# USB_SATA.net
KiCad netlist of a schematic drawn in Altium Designer
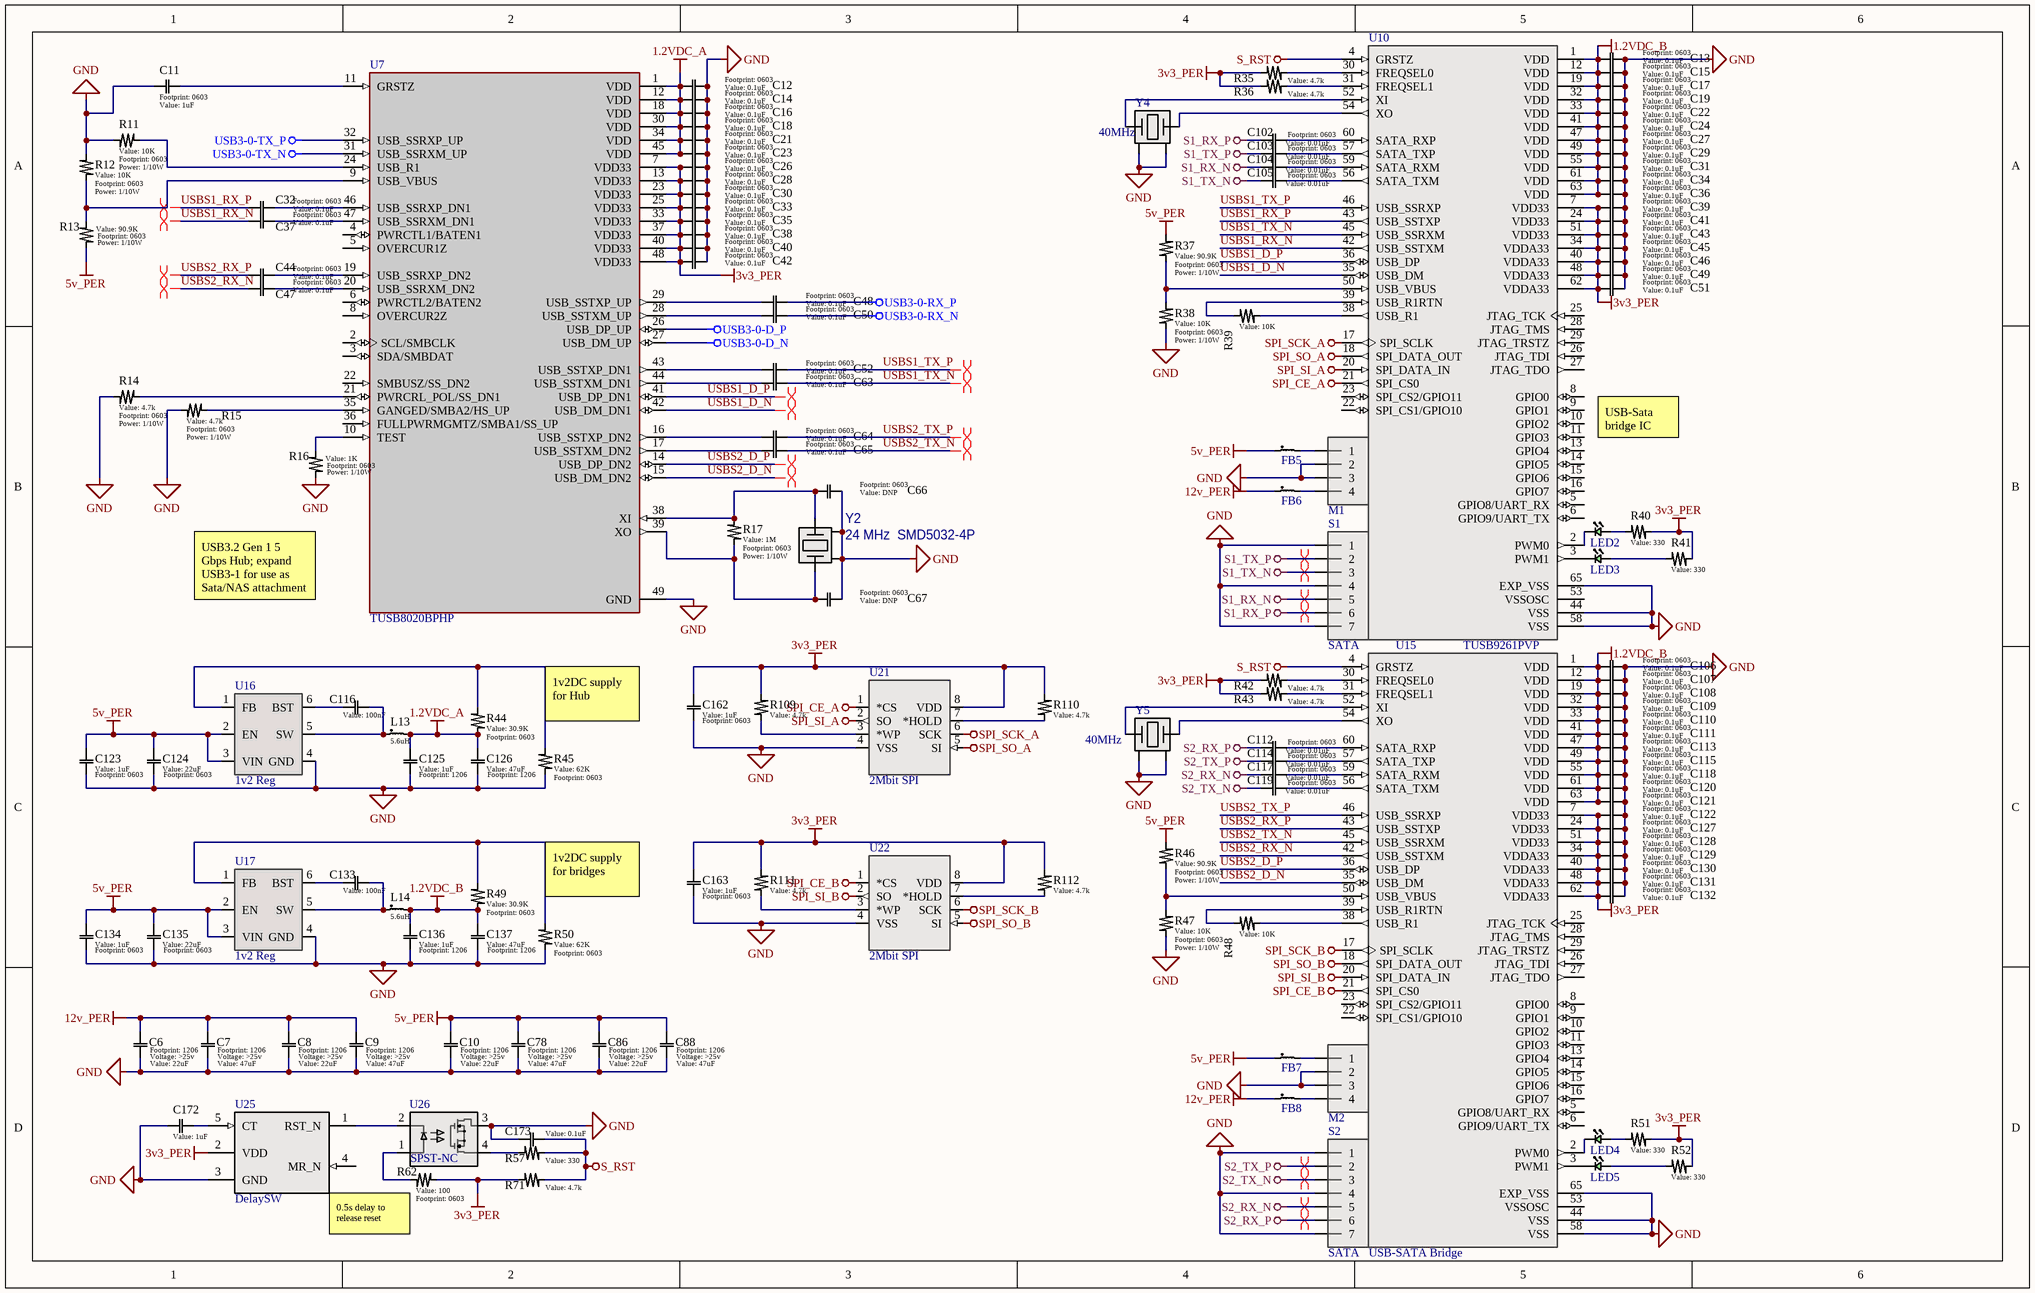
[diagram p0: USB_SATA.SchDoc]

(export (version "E")
  (design (tool "Eeschema 10.0.6"))
  (components
    (comp (ref "C6")
      (value "22uF")
      (footprint "1206")
      (fields
        (field (name "VOLTAGE") ">25v")
        (field (name "TOLERANCE") "20%")
        (field (name "Comment") "Generic Capacitor")
      )
      (libsource (lib "Capacitors") (part "Generic Capacitor"))
    )
    (comp (ref "C7")
      (value "47uF")
      (footprint "1206")
      (fields
        (field (name "VOLTAGE") ">25v")
        (field (name "TOLERANCE") "20%")
        (field (name "Comment") "Generic Capacitor")
      )
      (libsource (lib "Capacitors") (part "Generic Capacitor"))
    )
    (comp (ref "C8")
      (value "22uF")
      (footprint "1206")
      (fields
        (field (name "VOLTAGE") ">25v")
        (field (name "TOLERANCE") "20%")
        (field (name "Comment") "Generic Capacitor")
      )
      (libsource (lib "Capacitors") (part "Generic Capacitor"))
    )
    (comp (ref "C9")
      (value "47uF")
      (footprint "1206")
      (fields
        (field (name "VOLTAGE") ">25v")
        (field (name "TOLERANCE") "20%")
        (field (name "Comment") "Generic Capacitor")
      )
      (libsource (lib "Capacitors") (part "Generic Capacitor"))
    )
    (comp (ref "C10")
      (value "22uF")
      (footprint "1206")
      (fields
        (field (name "VOLTAGE") ">25v")
        (field (name "TOLERANCE") "20%")
        (field (name "Comment") "Generic Capacitor")
      )
      (libsource (lib "Capacitors") (part "Generic Capacitor"))
    )
    (comp (ref "C11")
      (value "1uF")
      (footprint "0603")
      (fields
        (field (name "VOLTAGE") ">10V")
        (field (name "TOLERANCE") "10%")
        (field (name "Comment") "Generic Capacitor")
      )
      (libsource (lib "Capacitors") (part "Generic Capacitor"))
    )
    (comp (ref "C12")
      (value "0.1uF")
      (footprint "0603")
      (fields
        (field (name "VOLTAGE") "10V")
        (field (name "TOLERANCE") "10%")
        (field (name "Comment") "Generic Capacitor")
      )
      (libsource (lib "Capacitors") (part "Generic Capacitor"))
    )
    (comp (ref "C13")
      (value "0.1uF")
      (footprint "0603")
      (fields
        (field (name "VOLTAGE") "10V")
        (field (name "TOLERANCE") "10%")
        (field (name "Comment") "Generic Capacitor")
      )
      (libsource (lib "Capacitors") (part "Generic Capacitor"))
    )
    (comp (ref "C14")
      (value "0.1uF")
      (footprint "0603")
      (fields
        (field (name "VOLTAGE") "10V")
        (field (name "TOLERANCE") "10%")
        (field (name "Comment") "Generic Capacitor")
      )
      (libsource (lib "Capacitors") (part "Generic Capacitor"))
    )
    (comp (ref "C15")
      (value "0.1uF")
      (footprint "0603")
      (fields
        (field (name "VOLTAGE") "10V")
        (field (name "TOLERANCE") "10%")
        (field (name "Comment") "Generic Capacitor")
      )
      (libsource (lib "Capacitors") (part "Generic Capacitor"))
    )
    (comp (ref "C16")
      (value "0.1uF")
      (footprint "0603")
      (fields
        (field (name "VOLTAGE") "10V")
        (field (name "TOLERANCE") "10%")
        (field (name "Comment") "Generic Capacitor")
      )
      (libsource (lib "Capacitors") (part "Generic Capacitor"))
    )
    (comp (ref "C17")
      (value "0.1uF")
      (footprint "0603")
      (fields
        (field (name "VOLTAGE") "10V")
        (field (name "TOLERANCE") "10%")
        (field (name "Comment") "Generic Capacitor")
      )
      (libsource (lib "Capacitors") (part "Generic Capacitor"))
    )
    (comp (ref "C18")
      (value "0.1uF")
      (footprint "0603")
      (fields
        (field (name "VOLTAGE") "10V")
        (field (name "TOLERANCE") "10%")
        (field (name "Comment") "Generic Capacitor")
      )
      (libsource (lib "Capacitors") (part "Generic Capacitor"))
    )
    (comp (ref "C19")
      (value "0.1uF")
      (footprint "0603")
      (fields
        (field (name "VOLTAGE") "10V")
        (field (name "TOLERANCE") "10%")
        (field (name "Comment") "Generic Capacitor")
      )
      (libsource (lib "Capacitors") (part "Generic Capacitor"))
    )
    (comp (ref "C21")
      (value "0.1uF")
      (footprint "0603")
      (fields
        (field (name "VOLTAGE") "10V")
        (field (name "TOLERANCE") "10%")
        (field (name "Comment") "Generic Capacitor")
      )
      (libsource (lib "Capacitors") (part "Generic Capacitor"))
    )
    (comp (ref "C22")
      (value "0.1uF")
      (footprint "0603")
      (fields
        (field (name "VOLTAGE") "10V")
        (field (name "TOLERANCE") "10%")
        (field (name "Comment") "Generic Capacitor")
      )
      (libsource (lib "Capacitors") (part "Generic Capacitor"))
    )
    (comp (ref "C23")
      (value "0.1uF")
      (footprint "0603")
      (fields
        (field (name "VOLTAGE") "10V")
        (field (name "TOLERANCE") "10%")
        (field (name "Comment") "Generic Capacitor")
      )
      (libsource (lib "Capacitors") (part "Generic Capacitor"))
    )
    (comp (ref "C24")
      (value "0.1uF")
      (footprint "0603")
      (fields
        (field (name "VOLTAGE") "10V")
        (field (name "TOLERANCE") "10%")
        (field (name "Comment") "Generic Capacitor")
      )
      (libsource (lib "Capacitors") (part "Generic Capacitor"))
    )
    (comp (ref "C26")
      (value "0.1uF")
      (footprint "0603")
      (fields
        (field (name "VOLTAGE") "10V")
        (field (name "TOLERANCE") "10%")
        (field (name "Comment") "Generic Capacitor")
      )
      (libsource (lib "Capacitors") (part "Generic Capacitor"))
    )
    (comp (ref "C27")
      (value "0.1uF")
      (footprint "0603")
      (fields
        (field (name "VOLTAGE") "10V")
        (field (name "TOLERANCE") "10%")
        (field (name "Comment") "Generic Capacitor")
      )
      (libsource (lib "Capacitors") (part "Generic Capacitor"))
    )
    (comp (ref "C28")
      (value "0.1uF")
      (footprint "0603")
      (fields
        (field (name "VOLTAGE") "10V")
        (field (name "TOLERANCE") "10%")
        (field (name "Comment") "Generic Capacitor")
      )
      (libsource (lib "Capacitors") (part "Generic Capacitor"))
    )
    (comp (ref "C29")
      (value "0.1uF")
      (footprint "0603")
      (fields
        (field (name "VOLTAGE") "10V")
        (field (name "TOLERANCE") "10%")
        (field (name "Comment") "Generic Capacitor")
      )
      (libsource (lib "Capacitors") (part "Generic Capacitor"))
    )
    (comp (ref "C30")
      (value "0.1uF")
      (footprint "0603")
      (fields
        (field (name "VOLTAGE") "10V")
        (field (name "TOLERANCE") "10%")
        (field (name "Comment") "Generic Capacitor")
      )
      (libsource (lib "Capacitors") (part "Generic Capacitor"))
    )
    (comp (ref "C31")
      (value "0.1uF")
      (footprint "0603")
      (fields
        (field (name "VOLTAGE") "10V")
        (field (name "TOLERANCE") "10%")
        (field (name "Comment") "Generic Capacitor")
      )
      (libsource (lib "Capacitors") (part "Generic Capacitor"))
    )
    (comp (ref "C32")
      (value "0.1uF")
      (footprint "0603")
      (fields
        (field (name "VOLTAGE") "10V")
        (field (name "TOLERANCE") "10%")
        (field (name "Comment") "Generic Capacitor")
      )
      (libsource (lib "Capacitors") (part "Generic Capacitor"))
    )
    (comp (ref "C33")
      (value "0.1uF")
      (footprint "0603")
      (fields
        (field (name "VOLTAGE") "10V")
        (field (name "TOLERANCE") "10%")
        (field (name "Comment") "Generic Capacitor")
      )
      (libsource (lib "Capacitors") (part "Generic Capacitor"))
    )
    (comp (ref "C34")
      (value "0.1uF")
      (footprint "0603")
      (fields
        (field (name "VOLTAGE") "10V")
        (field (name "TOLERANCE") "10%")
        (field (name "Comment") "Generic Capacitor")
      )
      (libsource (lib "Capacitors") (part "Generic Capacitor"))
    )
    (comp (ref "C35")
      (value "0.1uF")
      (footprint "0603")
      (fields
        (field (name "VOLTAGE") "10V")
        (field (name "TOLERANCE") "10%")
        (field (name "Comment") "Generic Capacitor")
      )
      (libsource (lib "Capacitors") (part "Generic Capacitor"))
    )
    (comp (ref "C36")
      (value "0.1uF")
      (footprint "0603")
      (fields
        (field (name "VOLTAGE") "10V")
        (field (name "TOLERANCE") "10%")
        (field (name "Comment") "Generic Capacitor")
      )
      (libsource (lib "Capacitors") (part "Generic Capacitor"))
    )
    (comp (ref "C37")
      (value "0.1uF")
      (footprint "0603")
      (fields
        (field (name "VOLTAGE") "10V")
        (field (name "TOLERANCE") "10%")
        (field (name "Comment") "Generic Capacitor")
      )
      (libsource (lib "Capacitors") (part "Generic Capacitor"))
    )
    (comp (ref "C38")
      (value "0.1uF")
      (footprint "0603")
      (fields
        (field (name "VOLTAGE") "10V")
        (field (name "TOLERANCE") "10%")
        (field (name "Comment") "Generic Capacitor")
      )
      (libsource (lib "Capacitors") (part "Generic Capacitor"))
    )
    (comp (ref "C39")
      (value "0.1uF")
      (footprint "0603")
      (fields
        (field (name "VOLTAGE") "10V")
        (field (name "TOLERANCE") "10%")
        (field (name "Comment") "Generic Capacitor")
      )
      (libsource (lib "Capacitors") (part "Generic Capacitor"))
    )
    (comp (ref "C40")
      (value "0.1uF")
      (footprint "0603")
      (fields
        (field (name "VOLTAGE") "10V")
        (field (name "TOLERANCE") "10%")
        (field (name "Comment") "Generic Capacitor")
      )
      (libsource (lib "Capacitors") (part "Generic Capacitor"))
    )
    (comp (ref "C41")
      (value "0.1uF")
      (footprint "0603")
      (fields
        (field (name "VOLTAGE") "10V")
        (field (name "TOLERANCE") "10%")
        (field (name "Comment") "Generic Capacitor")
      )
      (libsource (lib "Capacitors") (part "Generic Capacitor"))
    )
    (comp (ref "C42")
      (value "0.1uF")
      (footprint "0603")
      (fields
        (field (name "VOLTAGE") "10V")
        (field (name "TOLERANCE") "10%")
        (field (name "Comment") "Generic Capacitor")
      )
      (libsource (lib "Capacitors") (part "Generic Capacitor"))
    )
    (comp (ref "C43")
      (value "0.1uF")
      (footprint "0603")
      (fields
        (field (name "VOLTAGE") "10V")
        (field (name "TOLERANCE") "10%")
        (field (name "Comment") "Generic Capacitor")
      )
      (libsource (lib "Capacitors") (part "Generic Capacitor"))
    )
    (comp (ref "C44")
      (value "0.1uF")
      (footprint "0603")
      (fields
        (field (name "VOLTAGE") "10V")
        (field (name "TOLERANCE") "10%")
        (field (name "Comment") "Generic Capacitor")
      )
      (libsource (lib "Capacitors") (part "Generic Capacitor"))
    )
    (comp (ref "C45")
      (value "0.1uF")
      (footprint "0603")
      (fields
        (field (name "VOLTAGE") "10V")
        (field (name "TOLERANCE") "10%")
        (field (name "Comment") "Generic Capacitor")
      )
      (libsource (lib "Capacitors") (part "Generic Capacitor"))
    )
    (comp (ref "C46")
      (value "0.1uF")
      (footprint "0603")
      (fields
        (field (name "VOLTAGE") "10V")
        (field (name "TOLERANCE") "10%")
        (field (name "Comment") "Generic Capacitor")
      )
      (libsource (lib "Capacitors") (part "Generic Capacitor"))
    )
    (comp (ref "C47")
      (value "0.1uF")
      (footprint "0603")
      (fields
        (field (name "VOLTAGE") "10V")
        (field (name "TOLERANCE") "10%")
        (field (name "Comment") "Generic Capacitor")
      )
      (libsource (lib "Capacitors") (part "Generic Capacitor"))
    )
    (comp (ref "C48")
      (value "0.1uF")
      (footprint "0603")
      (fields
        (field (name "VOLTAGE") "10V")
        (field (name "TOLERANCE") "10%")
        (field (name "Comment") "Generic Capacitor")
      )
      (libsource (lib "Capacitors") (part "Generic Capacitor"))
    )
    (comp (ref "C49")
      (value "0.1uF")
      (footprint "0603")
      (fields
        (field (name "VOLTAGE") "10V")
        (field (name "TOLERANCE") "10%")
        (field (name "Comment") "Generic Capacitor")
      )
      (libsource (lib "Capacitors") (part "Generic Capacitor"))
    )
    (comp (ref "C50")
      (value "0.1uF")
      (footprint "0603")
      (fields
        (field (name "VOLTAGE") "10V")
        (field (name "TOLERANCE") "10%")
        (field (name "Comment") "Generic Capacitor")
      )
      (libsource (lib "Capacitors") (part "Generic Capacitor"))
    )
    (comp (ref "C51")
      (value "0.1uF")
      (footprint "0603")
      (fields
        (field (name "VOLTAGE") "10V")
        (field (name "TOLERANCE") "10%")
        (field (name "Comment") "Generic Capacitor")
      )
      (libsource (lib "Capacitors") (part "Generic Capacitor"))
    )
    (comp (ref "C52")
      (value "0.1uF")
      (footprint "0603")
      (fields
        (field (name "VOLTAGE") "10V")
        (field (name "TOLERANCE") "10%")
        (field (name "Comment") "Generic Capacitor")
      )
      (libsource (lib "Capacitors") (part "Generic Capacitor"))
    )
    (comp (ref "C63")
      (value "0.1uF")
      (footprint "0603")
      (fields
        (field (name "VOLTAGE") "10V")
        (field (name "TOLERANCE") "10%")
        (field (name "Comment") "Generic Capacitor")
      )
      (libsource (lib "Capacitors") (part "Generic Capacitor"))
    )
    (comp (ref "C64")
      (value "0.1uF")
      (footprint "0603")
      (fields
        (field (name "VOLTAGE") "10V")
        (field (name "TOLERANCE") "10%")
        (field (name "Comment") "Generic Capacitor")
      )
      (libsource (lib "Capacitors") (part "Generic Capacitor"))
    )
    (comp (ref "C65")
      (value "0.1uF")
      (footprint "0603")
      (fields
        (field (name "VOLTAGE") "10V")
        (field (name "TOLERANCE") "10%")
        (field (name "Comment") "Generic Capacitor")
      )
      (libsource (lib "Capacitors") (part "Generic Capacitor"))
    )
    (comp (ref "C66")
      (value "DNP")
      (footprint "0603")
      (fields
        (field (name "VOLTAGE") ">10V")
        (field (name "TOLERANCE") "10%")
        (field (name "Comment") "Generic Capacitor")
      )
      (libsource (lib "Capacitors") (part "Generic Capacitor"))
    )
    (comp (ref "C67")
      (value "DNP")
      (footprint "0603")
      (fields
        (field (name "VOLTAGE") ">10V")
        (field (name "TOLERANCE") "10%")
        (field (name "Comment") "Generic Capacitor")
      )
      (libsource (lib "Capacitors") (part "Generic Capacitor"))
    )
    (comp (ref "C78")
      (value "47uF")
      (footprint "1206")
      (fields
        (field (name "VOLTAGE") ">25v")
        (field (name "TOLERANCE") "20%")
        (field (name "Comment") "Generic Capacitor")
      )
      (libsource (lib "Capacitors") (part "Generic Capacitor"))
    )
    (comp (ref "C86")
      (value "22uF")
      (footprint "1206")
      (fields
        (field (name "VOLTAGE") ">25v")
        (field (name "TOLERANCE") "20%")
        (field (name "Comment") "Generic Capacitor")
      )
      (libsource (lib "Capacitors") (part "Generic Capacitor"))
    )
    (comp (ref "C88")
      (value "47uF")
      (footprint "1206")
      (fields
        (field (name "VOLTAGE") ">25v")
        (field (name "TOLERANCE") "20%")
        (field (name "Comment") "Generic Capacitor")
      )
      (libsource (lib "Capacitors") (part "Generic Capacitor"))
    )
    (comp (ref "C102")
      (value "0.01uF")
      (footprint "0603")
      (fields
        (field (name "VOLTAGE") "10V")
        (field (name "TOLERANCE") "10%")
        (field (name "Comment") "Generic Capacitor")
      )
      (libsource (lib "Capacitors") (part "Generic Capacitor"))
    )
    (comp (ref "C103")
      (value "0.01uF")
      (footprint "0603")
      (fields
        (field (name "VOLTAGE") "10V")
        (field (name "TOLERANCE") "10%")
        (field (name "Comment") "Generic Capacitor")
      )
      (libsource (lib "Capacitors") (part "Generic Capacitor"))
    )
    (comp (ref "C104")
      (value "0.01uF")
      (footprint "0603")
      (fields
        (field (name "VOLTAGE") "10V")
        (field (name "TOLERANCE") "10%")
        (field (name "Comment") "Generic Capacitor")
      )
      (libsource (lib "Capacitors") (part "Generic Capacitor"))
    )
    (comp (ref "C105")
      (value "0.01uF")
      (footprint "0603")
      (fields
        (field (name "VOLTAGE") "10V")
        (field (name "TOLERANCE") "10%")
        (field (name "Comment") "Generic Capacitor")
      )
      (libsource (lib "Capacitors") (part "Generic Capacitor"))
    )
    (comp (ref "C106")
      (value "0.1uF")
      (footprint "0603")
      (fields
        (field (name "VOLTAGE") "10V")
        (field (name "TOLERANCE") "10%")
        (field (name "Comment") "Generic Capacitor")
      )
      (libsource (lib "Capacitors") (part "Generic Capacitor"))
    )
    (comp (ref "C107")
      (value "0.1uF")
      (footprint "0603")
      (fields
        (field (name "VOLTAGE") "10V")
        (field (name "TOLERANCE") "10%")
        (field (name "Comment") "Generic Capacitor")
      )
      (libsource (lib "Capacitors") (part "Generic Capacitor"))
    )
    (comp (ref "C108")
      (value "0.1uF")
      (footprint "0603")
      (fields
        (field (name "VOLTAGE") "10V")
        (field (name "TOLERANCE") "10%")
        (field (name "Comment") "Generic Capacitor")
      )
      (libsource (lib "Capacitors") (part "Generic Capacitor"))
    )
    (comp (ref "C109")
      (value "0.1uF")
      (footprint "0603")
      (fields
        (field (name "VOLTAGE") "10V")
        (field (name "TOLERANCE") "10%")
        (field (name "Comment") "Generic Capacitor")
      )
      (libsource (lib "Capacitors") (part "Generic Capacitor"))
    )
    (comp (ref "C110")
      (value "0.1uF")
      (footprint "0603")
      (fields
        (field (name "VOLTAGE") "10V")
        (field (name "TOLERANCE") "10%")
        (field (name "Comment") "Generic Capacitor")
      )
      (libsource (lib "Capacitors") (part "Generic Capacitor"))
    )
    (comp (ref "C111")
      (value "0.1uF")
      (footprint "0603")
      (fields
        (field (name "VOLTAGE") "10V")
        (field (name "TOLERANCE") "10%")
        (field (name "Comment") "Generic Capacitor")
      )
      (libsource (lib "Capacitors") (part "Generic Capacitor"))
    )
    (comp (ref "C112")
      (value "0.01uF")
      (footprint "0603")
      (fields
        (field (name "VOLTAGE") "10V")
        (field (name "TOLERANCE") "10%")
        (field (name "Comment") "Generic Capacitor")
      )
      (libsource (lib "Capacitors") (part "Generic Capacitor"))
    )
    (comp (ref "C113")
      (value "0.1uF")
      (footprint "0603")
      (fields
        (field (name "VOLTAGE") "10V")
        (field (name "TOLERANCE") "10%")
        (field (name "Comment") "Generic Capacitor")
      )
      (libsource (lib "Capacitors") (part "Generic Capacitor"))
    )
    (comp (ref "C114")
      (value "0.01uF")
      (footprint "0603")
      (fields
        (field (name "VOLTAGE") "10V")
        (field (name "TOLERANCE") "10%")
        (field (name "Comment") "Generic Capacitor")
      )
      (libsource (lib "Capacitors") (part "Generic Capacitor"))
    )
    (comp (ref "C115")
      (value "0.1uF")
      (footprint "0603")
      (fields
        (field (name "VOLTAGE") "10V")
        (field (name "TOLERANCE") "10%")
        (field (name "Comment") "Generic Capacitor")
      )
      (libsource (lib "Capacitors") (part "Generic Capacitor"))
    )
    (comp (ref "C116")
      (value "100nF")
      (footprint "0603")
      (fields
        (field (name "VOLTAGE") ">10V")
        (field (name "TOLERANCE") "10%")
        (field (name "Comment") "Generic Capacitor")
      )
      (libsource (lib "Capacitors") (part "Generic Capacitor"))
    )
    (comp (ref "C117")
      (value "0.01uF")
      (footprint "0603")
      (fields
        (field (name "VOLTAGE") "10V")
        (field (name "TOLERANCE") "10%")
        (field (name "Comment") "Generic Capacitor")
      )
      (libsource (lib "Capacitors") (part "Generic Capacitor"))
    )
    (comp (ref "C118")
      (value "0.1uF")
      (footprint "0603")
      (fields
        (field (name "VOLTAGE") "10V")
        (field (name "TOLERANCE") "10%")
        (field (name "Comment") "Generic Capacitor")
      )
      (libsource (lib "Capacitors") (part "Generic Capacitor"))
    )
    (comp (ref "C119")
      (value "0.01uF")
      (footprint "0603")
      (fields
        (field (name "VOLTAGE") "10V")
        (field (name "TOLERANCE") "10%")
        (field (name "Comment") "Generic Capacitor")
      )
      (libsource (lib "Capacitors") (part "Generic Capacitor"))
    )
    (comp (ref "C120")
      (value "0.1uF")
      (footprint "0603")
      (fields
        (field (name "VOLTAGE") "10V")
        (field (name "TOLERANCE") "10%")
        (field (name "Comment") "Generic Capacitor")
      )
      (libsource (lib "Capacitors") (part "Generic Capacitor"))
    )
    (comp (ref "C121")
      (value "0.1uF")
      (footprint "0603")
      (fields
        (field (name "VOLTAGE") "10V")
        (field (name "TOLERANCE") "10%")
        (field (name "Comment") "Generic Capacitor")
      )
      (libsource (lib "Capacitors") (part "Generic Capacitor"))
    )
    (comp (ref "C122")
      (value "0.1uF")
      (footprint "0603")
      (fields
        (field (name "VOLTAGE") "10V")
        (field (name "TOLERANCE") "10%")
        (field (name "Comment") "Generic Capacitor")
      )
      (libsource (lib "Capacitors") (part "Generic Capacitor"))
    )
    (comp (ref "C123")
      (value "1uF")
      (footprint "0603")
      (fields
        (field (name "VOLTAGE") ">10V")
        (field (name "TOLERANCE") "10%")
        (field (name "Comment") "Generic Capacitor")
      )
      (libsource (lib "Capacitors") (part "Generic Capacitor"))
    )
    (comp (ref "C124")
      (value "22uF")
      (footprint "0603")
      (fields
        (field (name "VOLTAGE") ">10V")
        (field (name "TOLERANCE") "10%")
        (field (name "Comment") "Generic Capacitor")
      )
      (libsource (lib "Capacitors") (part "Generic Capacitor"))
    )
    (comp (ref "C125")
      (value "1uF")
      (footprint "1206")
      (fields
        (field (name "VOLTAGE") ">10V")
        (field (name "TOLERANCE") "10%")
        (field (name "Comment") "Generic Capacitor")
      )
      (libsource (lib "Capacitors") (part "Generic Capacitor"))
    )
    (comp (ref "C126")
      (value "47uF")
      (footprint "1206")
      (fields
        (field (name "VOLTAGE") ">10V")
        (field (name "TOLERANCE") "10%")
        (field (name "Comment") "Generic Capacitor")
      )
      (libsource (lib "Capacitors") (part "Generic Capacitor"))
    )
    (comp (ref "C127")
      (value "0.1uF")
      (footprint "0603")
      (fields
        (field (name "VOLTAGE") "10V")
        (field (name "TOLERANCE") "10%")
        (field (name "Comment") "Generic Capacitor")
      )
      (libsource (lib "Capacitors") (part "Generic Capacitor"))
    )
    (comp (ref "C128")
      (value "0.1uF")
      (footprint "0603")
      (fields
        (field (name "VOLTAGE") "10V")
        (field (name "TOLERANCE") "10%")
        (field (name "Comment") "Generic Capacitor")
      )
      (libsource (lib "Capacitors") (part "Generic Capacitor"))
    )
    (comp (ref "C129")
      (value "0.1uF")
      (footprint "0603")
      (fields
        (field (name "VOLTAGE") "10V")
        (field (name "TOLERANCE") "10%")
        (field (name "Comment") "Generic Capacitor")
      )
      (libsource (lib "Capacitors") (part "Generic Capacitor"))
    )
    (comp (ref "C130")
      (value "0.1uF")
      (footprint "0603")
      (fields
        (field (name "VOLTAGE") "10V")
        (field (name "TOLERANCE") "10%")
        (field (name "Comment") "Generic Capacitor")
      )
      (libsource (lib "Capacitors") (part "Generic Capacitor"))
    )
    (comp (ref "C131")
      (value "0.1uF")
      (footprint "0603")
      (fields
        (field (name "VOLTAGE") "10V")
        (field (name "TOLERANCE") "10%")
        (field (name "Comment") "Generic Capacitor")
      )
      (libsource (lib "Capacitors") (part "Generic Capacitor"))
    )
    (comp (ref "C132")
      (value "0.1uF")
      (footprint "0603")
      (fields
        (field (name "VOLTAGE") "10V")
        (field (name "TOLERANCE") "10%")
        (field (name "Comment") "Generic Capacitor")
      )
      (libsource (lib "Capacitors") (part "Generic Capacitor"))
    )
    (comp (ref "C133")
      (value "100nF")
      (footprint "0603")
      (fields
        (field (name "VOLTAGE") ">10V")
        (field (name "TOLERANCE") "10%")
        (field (name "Comment") "Generic Capacitor")
      )
      (libsource (lib "Capacitors") (part "Generic Capacitor"))
    )
    (comp (ref "C134")
      (value "1uF")
      (footprint "0603")
      (fields
        (field (name "VOLTAGE") ">10V")
        (field (name "TOLERANCE") "10%")
        (field (name "Comment") "Generic Capacitor")
      )
      (libsource (lib "Capacitors") (part "Generic Capacitor"))
    )
    (comp (ref "C135")
      (value "22uF")
      (footprint "0603")
      (fields
        (field (name "VOLTAGE") ">10V")
        (field (name "TOLERANCE") "10%")
        (field (name "Comment") "Generic Capacitor")
      )
      (libsource (lib "Capacitors") (part "Generic Capacitor"))
    )
    (comp (ref "C136")
      (value "1uF")
      (footprint "1206")
      (fields
        (field (name "VOLTAGE") ">10V")
        (field (name "TOLERANCE") "10%")
        (field (name "Comment") "Generic Capacitor")
      )
      (libsource (lib "Capacitors") (part "Generic Capacitor"))
    )
    (comp (ref "C137")
      (value "47uF")
      (footprint "1206")
      (fields
        (field (name "VOLTAGE") ">10V")
        (field (name "TOLERANCE") "10%")
        (field (name "Comment") "Generic Capacitor")
      )
      (libsource (lib "Capacitors") (part "Generic Capacitor"))
    )
    (comp (ref "C162")
      (value "1uF")
      (footprint "0603")
      (fields
        (field (name "VOLTAGE") ">10V")
        (field (name "TOLERANCE") "10%")
        (field (name "Comment") "Generic Capacitor")
      )
      (libsource (lib "Capacitors") (part "Generic Capacitor"))
    )
    (comp (ref "C163")
      (value "1uF")
      (footprint "0603")
      (fields
        (field (name "VOLTAGE") ">10V")
        (field (name "TOLERANCE") "10%")
        (field (name "Comment") "Generic Capacitor")
      )
      (libsource (lib "Capacitors") (part "Generic Capacitor"))
    )
    (comp (ref "C172")
      (value "1uF")
      (footprint "0603")
      (fields
        (field (name "VOLTAGE") "10V")
        (field (name "TOLERANCE") "10%")
        (field (name "Comment") "Generic Capacitor")
      )
      (libsource (lib "Capacitors") (part "Generic Capacitor"))
    )
    (comp (ref "C173")
      (value "0.1uF")
      (footprint "0603")
      (fields
        (field (name "VOLTAGE") "10V")
        (field (name "TOLERANCE") "10%")
        (field (name "Comment") "Generic Capacitor")
      )
      (libsource (lib "Capacitors") (part "Generic Capacitor"))
    )
    (comp (ref "FB5")
      (value "1206 Ferrite")
      (footprint "1206")
      (description "160 Ohms @ 100MHz 1 Power, Signal Line Ferrite Bead 1206 (3216 Metric) 6A 18mOhm")
      (libsource (lib "Inductors") (part "HI1206T161R-10"))
    )
    (comp (ref "FB6")
      (value "1206 Ferrite")
      (footprint "1206")
      (description "160 Ohms @ 100MHz 1 Power, Signal Line Ferrite Bead 1206 (3216 Metric) 6A 18mOhm")
      (libsource (lib "Inductors") (part "HI1206T161R-10"))
    )
    (comp (ref "FB7")
      (value "1206 Ferrite")
      (footprint "1206")
      (description "160 Ohms @ 100MHz 1 Power, Signal Line Ferrite Bead 1206 (3216 Metric) 6A 18mOhm")
      (libsource (lib "Inductors") (part "HI1206T161R-10"))
    )
    (comp (ref "FB8")
      (value "1206 Ferrite")
      (footprint "1206")
      (description "160 Ohms @ 100MHz 1 Power, Signal Line Ferrite Bead 1206 (3216 Metric) 6A 18mOhm")
      (libsource (lib "Inductors") (part "HI1206T161R-10"))
    )
    (comp (ref "L13")
      (value "5.6uH")
      (footprint "TMPC0402HP")
      (description "2A 5.6uH ±20% SMD Power Inductor")
      (libsource (lib "Inductors") (part "TMPC0402HP-5R6MG-Z02"))
    )
    (comp (ref "L14")
      (value "5.6uH")
      (footprint "TMPC0402HP")
      (description "2A 5.6uH ±20% SMD Power Inductor")
      (libsource (lib "Inductors") (part "TMPC0402HP-5R6MG-Z02"))
    )
    (comp (ref "LED2")
      (value "LTST-C191KGKT")
      (footprint "0603 (1608 Metric) Concave")
      (description "LED Uni-Color Green 574nm 2-Pin Chip LED T/R")
      (libsource (lib "Gamber - Johnson LLC") (part "LTST-C191KGKT"))
    )
    (comp (ref "LED3")
      (value "LTST-C191KGKT")
      (footprint "0603 (1608 Metric) Concave")
      (description "LED Uni-Color Green 574nm 2-Pin Chip LED T/R")
      (libsource (lib "Gamber - Johnson LLC") (part "LTST-C191KGKT"))
    )
    (comp (ref "LED4")
      (value "LTST-C191KGKT")
      (footprint "0603 (1608 Metric) Concave")
      (description "LED Uni-Color Green 574nm 2-Pin Chip LED T/R")
      (libsource (lib "Gamber - Johnson LLC") (part "LTST-C191KGKT"))
    )
    (comp (ref "LED5")
      (value "LTST-C191KGKT")
      (footprint "0603 (1608 Metric) Concave")
      (description "LED Uni-Color Green 574nm 2-Pin Chip LED T/R")
      (libsource (lib "Gamber - Johnson LLC") (part "LTST-C191KGKT"))
    )
    (comp (ref "M1")
      (value "MATE-n-Lock")
      (footprint "794287-1")
      (description "4 Position Header Connector 0.200\" (5.08mm) Through Hole Tin")
      (libsource (lib "Connectors") (part "794287-1"))
    )
    (comp (ref "M2")
      (value "MATE-n-Lock")
      (footprint "794287-1")
      (description "4 Position Header Connector 0.200\" (5.08mm) Through Hole Tin")
      (libsource (lib "Connectors") (part "794287-1"))
    )
    (comp (ref "R11")
      (value "10K")
      (footprint "0603")
      (fields
        (field (name "TOLERANCE") "1%")
        (field (name "POWER") "1/10W")
        (field (name "Comment") "Generic Resistor")
      )
      (libsource (lib "Resistors") (part "Generic Resistor"))
    )
    (comp (ref "R12")
      (value "10K")
      (footprint "0603")
      (fields
        (field (name "TOLERANCE") "1%")
        (field (name "POWER") "1/10W")
        (field (name "Comment") "Generic Resistor")
      )
      (libsource (lib "Resistors") (part "Generic Resistor"))
    )
    (comp (ref "R13")
      (value "90.9K")
      (footprint "0603")
      (fields
        (field (name "TOLERANCE") "1%")
        (field (name "POWER") "1/10W")
        (field (name "Comment") "Generic Resistor")
      )
      (libsource (lib "Resistors") (part "Generic Resistor"))
    )
    (comp (ref "R14")
      (value "4.7k")
      (footprint "0603")
      (fields
        (field (name "TOLERANCE") "1%")
        (field (name "POWER") "1/10W")
        (field (name "Comment") "Generic Resistor")
      )
      (libsource (lib "Resistors") (part "Generic Resistor"))
    )
    (comp (ref "R15")
      (value "4.7k")
      (footprint "0603")
      (fields
        (field (name "TOLERANCE") "1%")
        (field (name "POWER") "1/10W")
        (field (name "Comment") "Generic Resistor")
      )
      (libsource (lib "Resistors") (part "Generic Resistor"))
    )
    (comp (ref "R16")
      (value "1K")
      (footprint "0603")
      (fields
        (field (name "TOLERANCE") "1%")
        (field (name "POWER") "1/10W")
        (field (name "Comment") "Generic Resistor")
      )
      (libsource (lib "Resistors") (part "Generic Resistor"))
    )
    (comp (ref "R17")
      (value "1M")
      (footprint "0603")
      (fields
        (field (name "TOLERANCE") "1%")
        (field (name "POWER") "1/10W")
        (field (name "Comment") "Generic Resistor")
      )
      (libsource (lib "Resistors") (part "Generic Resistor"))
    )
    (comp (ref "R35")
      (value "4.7k")
      (footprint "0603")
      (fields
        (field (name "TOLERANCE") "1%")
        (field (name "POWER") "1/10W")
        (field (name "Comment") "Generic Resistor")
      )
      (libsource (lib "Resistors") (part "Generic Resistor"))
    )
    (comp (ref "R36")
      (value "4.7k")
      (footprint "0603")
      (fields
        (field (name "TOLERANCE") "1%")
        (field (name "POWER") "1/10W")
        (field (name "Comment") "Generic Resistor")
      )
      (libsource (lib "Resistors") (part "Generic Resistor"))
    )
    (comp (ref "R37")
      (value "90.9K")
      (footprint "0603")
      (fields
        (field (name "TOLERANCE") "1%")
        (field (name "POWER") "1/10W")
        (field (name "Comment") "Generic Resistor")
      )
      (libsource (lib "Resistors") (part "Generic Resistor"))
    )
    (comp (ref "R38")
      (value "10K")
      (footprint "0603")
      (fields
        (field (name "TOLERANCE") "1%")
        (field (name "POWER") "1/10W")
        (field (name "Comment") "Generic Resistor")
      )
      (libsource (lib "Resistors") (part "Generic Resistor"))
    )
    (comp (ref "R39")
      (value "10K")
      (footprint "0603")
      (fields
        (field (name "TOLERANCE") "1%")
        (field (name "POWER") "1/10W")
        (field (name "Comment") "Generic Resistor")
      )
      (libsource (lib "Resistors") (part "Generic Resistor"))
    )
    (comp (ref "R40")
      (value "330")
      (footprint "0603")
      (fields
        (field (name "TOLERANCE") "1%")
        (field (name "POWER") "1/10W")
        (field (name "Comment") "Generic Resistor")
      )
      (libsource (lib "Resistors") (part "Generic Resistor"))
    )
    (comp (ref "R41")
      (value "330")
      (footprint "0603")
      (fields
        (field (name "TOLERANCE") "1%")
        (field (name "POWER") "1/10W")
        (field (name "Comment") "Generic Resistor")
      )
      (libsource (lib "Resistors") (part "Generic Resistor"))
    )
    (comp (ref "R42")
      (value "4.7k")
      (footprint "0603")
      (fields
        (field (name "TOLERANCE") "1%")
        (field (name "POWER") "1/10W")
        (field (name "Comment") "Generic Resistor")
      )
      (libsource (lib "Resistors") (part "Generic Resistor"))
    )
    (comp (ref "R43")
      (value "4.7k")
      (footprint "0603")
      (fields
        (field (name "TOLERANCE") "1%")
        (field (name "POWER") "1/10W")
        (field (name "Comment") "Generic Resistor")
      )
      (libsource (lib "Resistors") (part "Generic Resistor"))
    )
    (comp (ref "R44")
      (value "30.9K")
      (footprint "0603")
      (fields
        (field (name "TOLERANCE") "1%")
        (field (name "POWER") "1/10W")
        (field (name "Comment") "Generic Resistor")
      )
      (libsource (lib "Resistors") (part "Generic Resistor"))
    )
    (comp (ref "R45")
      (value "62K")
      (footprint "0603")
      (fields
        (field (name "TOLERANCE") "1%")
        (field (name "POWER") "1/10W")
        (field (name "Comment") "Generic Resistor")
      )
      (libsource (lib "Resistors") (part "Generic Resistor"))
    )
    (comp (ref "R46")
      (value "90.9K")
      (footprint "0603")
      (fields
        (field (name "TOLERANCE") "1%")
        (field (name "POWER") "1/10W")
        (field (name "Comment") "Generic Resistor")
      )
      (libsource (lib "Resistors") (part "Generic Resistor"))
    )
    (comp (ref "R47")
      (value "10K")
      (footprint "0603")
      (fields
        (field (name "TOLERANCE") "1%")
        (field (name "POWER") "1/10W")
        (field (name "Comment") "Generic Resistor")
      )
      (libsource (lib "Resistors") (part "Generic Resistor"))
    )
    (comp (ref "R48")
      (value "10K")
      (footprint "0603")
      (fields
        (field (name "TOLERANCE") "1%")
        (field (name "POWER") "1/10W")
        (field (name "Comment") "Generic Resistor")
      )
      (libsource (lib "Resistors") (part "Generic Resistor"))
    )
    (comp (ref "R49")
      (value "30.9K")
      (footprint "0603")
      (fields
        (field (name "TOLERANCE") "1%")
        (field (name "POWER") "1/10W")
        (field (name "Comment") "Generic Resistor")
      )
      (libsource (lib "Resistors") (part "Generic Resistor"))
    )
    (comp (ref "R50")
      (value "62K")
      (footprint "0603")
      (fields
        (field (name "TOLERANCE") "1%")
        (field (name "POWER") "1/10W")
        (field (name "Comment") "Generic Resistor")
      )
      (libsource (lib "Resistors") (part "Generic Resistor"))
    )
    (comp (ref "R51")
      (value "330")
      (footprint "0603")
      (fields
        (field (name "TOLERANCE") "1%")
        (field (name "POWER") "1/10W")
        (field (name "Comment") "Generic Resistor")
      )
      (libsource (lib "Resistors") (part "Generic Resistor"))
    )
    (comp (ref "R52")
      (value "330")
      (footprint "0603")
      (fields
        (field (name "TOLERANCE") "1%")
        (field (name "POWER") "1/10W")
        (field (name "Comment") "Generic Resistor")
      )
      (libsource (lib "Resistors") (part "Generic Resistor"))
    )
    (comp (ref "R57")
      (value "330")
      (footprint "0603")
      (fields
        (field (name "TOLERANCE") "1%")
        (field (name "POWER") "1/10W")
        (field (name "Comment") "Generic Resistor")
      )
      (libsource (lib "Resistors") (part "Generic Resistor"))
    )
    (comp (ref "R62")
      (value "100")
      (footprint "0603")
      (fields
        (field (name "TOLERANCE") "1%")
        (field (name "POWER") "1/10W")
        (field (name "Comment") "Generic Resistor")
      )
      (libsource (lib "Resistors") (part "Generic Resistor"))
    )
    (comp (ref "R71")
      (value "4.7k")
      (footprint "0603")
      (fields
        (field (name "TOLERANCE") "1%")
        (field (name "POWER") "1/10W")
        (field (name "Comment") "Generic Resistor")
      )
      (libsource (lib "Resistors") (part "Generic Resistor"))
    )
    (comp (ref "R109")
      (value "4.7k")
      (footprint "0603")
      (fields
        (field (name "TOLERANCE") "1%")
        (field (name "POWER") "1/10W")
        (field (name "Comment") "Generic Resistor")
      )
      (libsource (lib "Resistors") (part "Generic Resistor"))
    )
    (comp (ref "R110")
      (value "4.7k")
      (footprint "0603")
      (fields
        (field (name "TOLERANCE") "1%")
        (field (name "POWER") "1/10W")
        (field (name "Comment") "Generic Resistor")
      )
      (libsource (lib "Resistors") (part "Generic Resistor"))
    )
    (comp (ref "R111")
      (value "4.7k")
      (footprint "0603")
      (fields
        (field (name "TOLERANCE") "1%")
        (field (name "POWER") "1/10W")
        (field (name "Comment") "Generic Resistor")
      )
      (libsource (lib "Resistors") (part "Generic Resistor"))
    )
    (comp (ref "R112")
      (value "4.7k")
      (footprint "0603")
      (fields
        (field (name "TOLERANCE") "1%")
        (field (name "POWER") "1/10W")
        (field (name "Comment") "Generic Resistor")
      )
      (libsource (lib "Resistors") (part "Generic Resistor"))
    )
    (comp (ref "S1")
      (value "SATA")
      (footprint "67800-8025")
      (description "7 Position SATA Header, Shrouded Connector Solder Through Hole")
      (libsource (lib "Connectors") (part "67800-8025"))
    )
    (comp (ref "S2")
      (value "SATA")
      (footprint "67800-8025")
      (description "7 Position SATA Header, Shrouded Connector Solder Through Hole")
      (libsource (lib "Connectors") (part "67800-8025"))
    )
    (comp (ref "U7")
      (value "TUSB8020BPHP")
      (footprint "HTQFP-48(7x7)")
      (description "USB Hub Controller USB 3.0")
      (libsource (lib "Misc ICs") (part "TUSB8020BPHP"))
    )
    (comp (ref "U10")
      (value "USB-SATA Bridge")
      (footprint "64-HTQFP (7x7)")
      (description "HDD, CD, DVD Drive Interface 64-HTQFP _7x7_")
      (fields
        (field (name "MF") "Texas Instruments")
        (field (name "DIGI-KEY_PART_NUMBER") "296-28827-ND")
        (field (name "MP") "TUSB9261PVP")
      )
      (libsource (lib "Misc ICs") (part "TUSB9261PVP"))
    )
    (comp (ref "U15")
      (value "USB-SATA Bridge")
      (footprint "64-HTQFP (7x7)")
      (description "HDD, CD, DVD Drive Interface 64-HTQFP _7x7_")
      (fields (field (name "MF") "Texas Instruments") (field (name "DIGI-KEY_PART_NUMBER") "296-28827-ND"))
      (libsource (lib "Misc ICs") (part "TUSB9261PVP"))
    )
    (comp (ref "U16")
      (value "1v2 Reg")
      (footprint "TSOT-23-6")
      (description "Step-down type Adjustable 2A 1.2V~12V 3.8V~32V TSOT-23-6 DC-DC Converter")
      (libsource (lib "Regulators") (part "AP63201WU-7"))
    )
    (comp (ref "U17")
      (value "1v2 Reg")
      (footprint "TSOT-23-6")
      (description "Step-down type Adjustable 2A 1.2V~12V 3.8V~32V TSOT-23-6 DC-DC Converter")
      (libsource (lib "Regulators") (part "AP63201WU-7"))
    )
    (comp (ref "U21")
      (value "2Mbit SPI")
      (footprint "8-SOIC (0.154\", 3.90mm Width)")
      (description "IC FLASH 2MBIT SPI 30MHZ 8SOP")
      (libsource (lib "Misc ICs") (part "LE25U20AMB-AH"))
    )
    (comp (ref "U22")
      (value "2Mbit SPI")
      (footprint "8-SOIC (0.154\", 3.90mm Width)")
      (description "IC FLASH 2MBIT SPI 30MHZ 8SOP")
      (libsource (lib "Misc ICs") (part "LE25U20AMB-AH"))
    )
    (comp (ref "U25")
      (value "DelaySW")
      (footprint "TSOT-23-5")
      (description "Supervisor Open Drain or Open Collector 1 Channel SOT-23-5\r\n2.2V Threshold")
      (libsource (lib "Switches") (part "TPS3840DL22DBVR"))
    )
    (comp (ref "U26")
      (value "SPST-NC")
      (footprint "4-SOP")
      (description "SSR RELAY SPST-NC 400MA 0-60V")
      (libsource (lib "Switches") (part "CPC1117N"))
    )
    (comp (ref "Y2")
      (value "24 MHz  SMD5032-4P")
      (footprint "ECS-240-18-30BQ-DS")
      (description "24 MHz ±30ppm Crystal 18pF 30 Ohms 4-SMD, No Lead")
      (libsource (lib "Gamber - Johnson LLC") (part "ECS-240-18-30BQ-DS"))
    )
    (comp (ref "Y4")
      (value "40MHz")
      (footprint "SMD3225-4P")
      (description "40MHz Surface Mount Crystal 10pF ±10ppm SMD3225-4P Crystal")
      (libsource (lib "Clock ICs") (part "L327S400H11L"))
    )
    (comp (ref "Y5")
      (value "40MHz")
      (footprint "SMD3225-4P")
      (description "40MHz Surface Mount Crystal 10pF ±10ppm SMD3225-4P Crystal")
      (libsource (lib "Clock ICs") (part "L327S400H11L"))
    )
  )
  (nets
    (net (code "1") (name "/USBS1_D_N") (class "Default")
      (node (ref "U10") (pin "35") (pinfunction "USB_DM_35") (pintype "bidirectional"))
      (node (ref "U7") (pin "42") (pinfunction "USB_DM_DN1_42") (pintype "bidirectional"))
    )
    (net (code "2") (name "/USBS1_D_P") (class "Default")
      (node (ref "U10") (pin "36") (pinfunction "USB_DP_36") (pintype "bidirectional"))
      (node (ref "U7") (pin "41") (pinfunction "USB_DP_DN1_41") (pintype "bidirectional"))
    )
    (net (code "3") (name "/USBS1_RX_N") (class "Default")
      (node (ref "C37") (pin "2") (pinfunction "2_2") (pintype "passive"))
      (node (ref "U10") (pin "42") (pinfunction "USB_SSTXM_42") (pintype "output"))
    )
    (net (code "4") (name "/USBS1_RX_P") (class "Default")
      (node (ref "C32") (pin "2") (pinfunction "2_2") (pintype "passive"))
      (node (ref "U10") (pin "43") (pinfunction "USB_SSTXP_43") (pintype "output"))
    )
    (net (code "5") (name "/USBS1_TX_N") (class "Default")
      (node (ref "C63") (pin "1") (pinfunction "1_1") (pintype "passive"))
      (node (ref "U10") (pin "45") (pinfunction "USB_SSRXM_45") (pintype "input"))
    )
    (net (code "6") (name "/USBS1_TX_P") (class "Default")
      (node (ref "C52") (pin "1") (pinfunction "1_1") (pintype "passive"))
      (node (ref "U10") (pin "46") (pinfunction "USB_SSRXP_46") (pintype "input"))
    )
    (net (code "7") (name "/USBS2_D_N") (class "Default")
      (node (ref "U15") (pin "35") (pinfunction "USB_DM_35") (pintype "bidirectional"))
      (node (ref "U7") (pin "15") (pinfunction "USB_DM_DN2_15") (pintype "bidirectional"))
    )
    (net (code "8") (name "/USBS2_D_P") (class "Default")
      (node (ref "U15") (pin "36") (pinfunction "USB_DP_36") (pintype "bidirectional"))
      (node (ref "U7") (pin "14") (pinfunction "USB_DP_DN2_14") (pintype "bidirectional"))
    )
    (net (code "9") (name "/USBS2_RX_N") (class "Default")
      (node (ref "C47") (pin "2") (pinfunction "2_2") (pintype "passive"))
      (node (ref "U15") (pin "42") (pinfunction "USB_SSTXM_42") (pintype "output"))
    )
    (net (code "10") (name "/USBS2_RX_P") (class "Default")
      (node (ref "C44") (pin "2") (pinfunction "2_2") (pintype "passive"))
      (node (ref "U15") (pin "43") (pinfunction "USB_SSTXP_43") (pintype "output"))
    )
    (net (code "11") (name "/USBS2_TX_N") (class "Default")
      (node (ref "C65") (pin "1") (pinfunction "1_1") (pintype "passive"))
      (node (ref "U15") (pin "45") (pinfunction "USB_SSRXM_45") (pintype "input"))
    )
    (net (code "12") (name "/USBS2_TX_P") (class "Default")
      (node (ref "C64") (pin "1") (pinfunction "1_1") (pintype "passive"))
      (node (ref "U15") (pin "46") (pinfunction "USB_SSRXP_46") (pintype "input"))
    )
    (net (code "13") (name "1.2VDC_A") (class "Default")
      (node (ref "C12") (pin "2") (pinfunction "2_2") (pintype "passive"))
      (node (ref "C125") (pin "1") (pinfunction "1_1") (pintype "passive"))
      (node (ref "C126") (pin "1") (pinfunction "1_1") (pintype "passive"))
      (node (ref "C14") (pin "2") (pinfunction "2_2") (pintype "passive"))
      (node (ref "C16") (pin "2") (pinfunction "2_2") (pintype "passive"))
      (node (ref "C18") (pin "2") (pinfunction "2_2") (pintype "passive"))
      (node (ref "C21") (pin "2") (pinfunction "2_2") (pintype "passive"))
      (node (ref "C23") (pin "2") (pinfunction "2_2") (pintype "passive"))
      (node (ref "L13") (pin "2") (pinfunction "2_2") (pintype "passive"))
      (node (ref "R44") (pin "1") (pinfunction "1_1") (pintype "passive"))
      (node (ref "U7") (pin "1") (pinfunction "VDD_1") (pintype "power_in"))
      (node (ref "U7") (pin "12") (pinfunction "VDD_12") (pintype "power_in"))
      (node (ref "U7") (pin "18") (pinfunction "VDD_18") (pintype "power_in"))
      (node (ref "U7") (pin "30") (pinfunction "VDD_30") (pintype "power_in"))
      (node (ref "U7") (pin "34") (pinfunction "VDD_34") (pintype "power_in"))
      (node (ref "U7") (pin "45") (pinfunction "VDD_45") (pintype "power_in"))
    )
    (net (code "14") (name "1.2VDC_B") (class "Default")
      (node (ref "C106") (pin "2") (pinfunction "2_2") (pintype "passive"))
      (node (ref "C107") (pin "2") (pinfunction "2_2") (pintype "passive"))
      (node (ref "C108") (pin "2") (pinfunction "2_2") (pintype "passive"))
      (node (ref "C109") (pin "2") (pinfunction "2_2") (pintype "passive"))
      (node (ref "C110") (pin "2") (pinfunction "2_2") (pintype "passive"))
      (node (ref "C111") (pin "2") (pinfunction "2_2") (pintype "passive"))
      (node (ref "C113") (pin "2") (pinfunction "2_2") (pintype "passive"))
      (node (ref "C115") (pin "2") (pinfunction "2_2") (pintype "passive"))
      (node (ref "C118") (pin "2") (pinfunction "2_2") (pintype "passive"))
      (node (ref "C120") (pin "2") (pinfunction "2_2") (pintype "passive"))
      (node (ref "C121") (pin "2") (pinfunction "2_2") (pintype "passive"))
      (node (ref "C13") (pin "2") (pinfunction "2_2") (pintype "passive"))
      (node (ref "C136") (pin "1") (pinfunction "1_1") (pintype "passive"))
      (node (ref "C137") (pin "1") (pinfunction "1_1") (pintype "passive"))
      (node (ref "C15") (pin "2") (pinfunction "2_2") (pintype "passive"))
      (node (ref "C17") (pin "2") (pinfunction "2_2") (pintype "passive"))
      (node (ref "C19") (pin "2") (pinfunction "2_2") (pintype "passive"))
      (node (ref "C22") (pin "2") (pinfunction "2_2") (pintype "passive"))
      (node (ref "C24") (pin "2") (pinfunction "2_2") (pintype "passive"))
      (node (ref "C27") (pin "2") (pinfunction "2_2") (pintype "passive"))
      (node (ref "C29") (pin "2") (pinfunction "2_2") (pintype "passive"))
      (node (ref "C31") (pin "2") (pinfunction "2_2") (pintype "passive"))
      (node (ref "C34") (pin "2") (pinfunction "2_2") (pintype "passive"))
      (node (ref "C36") (pin "2") (pinfunction "2_2") (pintype "passive"))
      (node (ref "L14") (pin "2") (pinfunction "2_2") (pintype "passive"))
      (node (ref "R49") (pin "1") (pinfunction "1_1") (pintype "passive"))
      (node (ref "U10") (pin "1") (pinfunction "VDD_1") (pintype "power_in"))
      (node (ref "U10") (pin "12") (pinfunction "VDD_12") (pintype "power_in"))
      (node (ref "U10") (pin "19") (pinfunction "VDD_19") (pintype "power_in"))
      (node (ref "U10") (pin "32") (pinfunction "VDD_32") (pintype "power_in"))
      (node (ref "U10") (pin "33") (pinfunction "VDD_33") (pintype "power_in"))
      (node (ref "U10") (pin "41") (pinfunction "VDD_41") (pintype "power_in"))
      (node (ref "U10") (pin "47") (pinfunction "VDD_47") (pintype "power_in"))
      (node (ref "U10") (pin "49") (pinfunction "VDD_49") (pintype "power_in"))
      (node (ref "U10") (pin "55") (pinfunction "VDD_55") (pintype "power_in"))
      (node (ref "U10") (pin "61") (pinfunction "VDD_61") (pintype "power_in"))
      (node (ref "U10") (pin "63") (pinfunction "VDD_63") (pintype "power_in"))
      (node (ref "U15") (pin "1") (pinfunction "VDD_1") (pintype "power_in"))
      (node (ref "U15") (pin "12") (pinfunction "VDD_12") (pintype "power_in"))
      (node (ref "U15") (pin "19") (pinfunction "VDD_19") (pintype "power_in"))
      (node (ref "U15") (pin "32") (pinfunction "VDD_32") (pintype "power_in"))
      (node (ref "U15") (pin "33") (pinfunction "VDD_33") (pintype "power_in"))
      (node (ref "U15") (pin "41") (pinfunction "VDD_41") (pintype "power_in"))
      (node (ref "U15") (pin "47") (pinfunction "VDD_47") (pintype "power_in"))
      (node (ref "U15") (pin "49") (pinfunction "VDD_49") (pintype "power_in"))
      (node (ref "U15") (pin "55") (pinfunction "VDD_55") (pintype "power_in"))
      (node (ref "U15") (pin "61") (pinfunction "VDD_61") (pintype "power_in"))
      (node (ref "U15") (pin "63") (pinfunction "VDD_63") (pintype "power_in"))
    )
    (net (code "15") (name "3v3_PER") (class "Default")
      (node (ref "C122") (pin "2") (pinfunction "2_2") (pintype "passive"))
      (node (ref "C127") (pin "2") (pinfunction "2_2") (pintype "passive"))
      (node (ref "C128") (pin "2") (pinfunction "2_2") (pintype "passive"))
      (node (ref "C129") (pin "2") (pinfunction "2_2") (pintype "passive"))
      (node (ref "C130") (pin "2") (pinfunction "2_2") (pintype "passive"))
      (node (ref "C131") (pin "2") (pinfunction "2_2") (pintype "passive"))
      (node (ref "C132") (pin "2") (pinfunction "2_2") (pintype "passive"))
      (node (ref "C162") (pin "1") (pinfunction "1_1") (pintype "passive"))
      (node (ref "C163") (pin "1") (pinfunction "1_1") (pintype "passive"))
      (node (ref "C26") (pin "2") (pinfunction "2_2") (pintype "passive"))
      (node (ref "C28") (pin "2") (pinfunction "2_2") (pintype "passive"))
      (node (ref "C30") (pin "2") (pinfunction "2_2") (pintype "passive"))
      (node (ref "C33") (pin "2") (pinfunction "2_2") (pintype "passive"))
      (node (ref "C35") (pin "2") (pinfunction "2_2") (pintype "passive"))
      (node (ref "C38") (pin "2") (pinfunction "2_2") (pintype "passive"))
      (node (ref "C39") (pin "2") (pinfunction "2_2") (pintype "passive"))
      (node (ref "C40") (pin "2") (pinfunction "2_2") (pintype "passive"))
      (node (ref "C41") (pin "2") (pinfunction "2_2") (pintype "passive"))
      (node (ref "C42") (pin "2") (pinfunction "2_2") (pintype "passive"))
      (node (ref "C43") (pin "2") (pinfunction "2_2") (pintype "passive"))
      (node (ref "C45") (pin "2") (pinfunction "2_2") (pintype "passive"))
      (node (ref "C46") (pin "2") (pinfunction "2_2") (pintype "passive"))
      (node (ref "C49") (pin "2") (pinfunction "2_2") (pintype "passive"))
      (node (ref "C51") (pin "2") (pinfunction "2_2") (pintype "passive"))
      (node (ref "R109") (pin "1") (pinfunction "1_1") (pintype "passive"))
      (node (ref "R110") (pin "1") (pinfunction "1_1") (pintype "passive"))
      (node (ref "R111") (pin "1") (pinfunction "1_1") (pintype "passive"))
      (node (ref "R112") (pin "1") (pinfunction "1_1") (pintype "passive"))
      (node (ref "R35") (pin "1") (pinfunction "1_1") (pintype "passive"))
      (node (ref "R36") (pin "1") (pinfunction "1_1") (pintype "passive"))
      (node (ref "R40") (pin "2") (pinfunction "2_2") (pintype "passive"))
      (node (ref "R41") (pin "2") (pinfunction "2_2") (pintype "passive"))
      (node (ref "R42") (pin "1") (pinfunction "1_1") (pintype "passive"))
      (node (ref "R43") (pin "1") (pinfunction "1_1") (pintype "passive"))
      (node (ref "R51") (pin "2") (pinfunction "2_2") (pintype "passive"))
      (node (ref "R52") (pin "2") (pinfunction "2_2") (pintype "passive"))
      (node (ref "R62") (pin "2") (pinfunction "2_2") (pintype "passive"))
      (node (ref "R71") (pin "1") (pinfunction "1_1") (pintype "passive"))
      (node (ref "U10") (pin "24") (pinfunction "VDD33_24") (pintype "power_in"))
      (node (ref "U10") (pin "34") (pinfunction "VDDA33_34") (pintype "power_in"))
      (node (ref "U10") (pin "40") (pinfunction "VDDA33_40") (pintype "power_in"))
      (node (ref "U10") (pin "48") (pinfunction "VDDA33_48") (pintype "power_in"))
      (node (ref "U10") (pin "51") (pinfunction "VDD33_51") (pintype "power_in"))
      (node (ref "U10") (pin "62") (pinfunction "VDDA33_62") (pintype "power_in"))
      (node (ref "U10") (pin "7") (pinfunction "VDD33_7") (pintype "power_in"))
      (node (ref "U15") (pin "24") (pinfunction "VDD33_24") (pintype "power_in"))
      (node (ref "U15") (pin "34") (pinfunction "VDDA33_34") (pintype "power_in"))
      (node (ref "U15") (pin "40") (pinfunction "VDDA33_40") (pintype "power_in"))
      (node (ref "U15") (pin "48") (pinfunction "VDDA33_48") (pintype "power_in"))
      (node (ref "U15") (pin "51") (pinfunction "VDD33_51") (pintype "power_in"))
      (node (ref "U15") (pin "62") (pinfunction "VDDA33_62") (pintype "power_in"))
      (node (ref "U15") (pin "7") (pinfunction "VDD33_7") (pintype "power_in"))
      (node (ref "U21") (pin "8") (pinfunction "VDD_8") (pintype "power_in"))
      (node (ref "U22") (pin "8") (pinfunction "VDD_8") (pintype "power_in"))
      (node (ref "U25") (pin "2") (pinfunction "VDD_2") (pintype "power_in"))
      (node (ref "U7") (pin "13") (pinfunction "VDD33_13") (pintype "power_in"))
      (node (ref "U7") (pin "23") (pinfunction "VDD33_23") (pintype "power_in"))
      (node (ref "U7") (pin "25") (pinfunction "VDD33_25") (pintype "power_in"))
      (node (ref "U7") (pin "33") (pinfunction "VDD33_33") (pintype "power_in"))
      (node (ref "U7") (pin "37") (pinfunction "VDD33_37") (pintype "power_in"))
      (node (ref "U7") (pin "40") (pinfunction "VDD33_40") (pintype "power_in"))
      (node (ref "U7") (pin "48") (pinfunction "VDD33_48") (pintype "power_in"))
      (node (ref "U7") (pin "7") (pinfunction "VDD33_7") (pintype "power_in"))
    )
    (net (code "16") (name "5v_PER") (class "Default")
      (node (ref "C10") (pin "1") (pinfunction "1_1") (pintype "passive"))
      (node (ref "C123") (pin "1") (pinfunction "1_1") (pintype "passive"))
      (node (ref "C124") (pin "1") (pinfunction "1_1") (pintype "passive"))
      (node (ref "C134") (pin "1") (pinfunction "1_1") (pintype "passive"))
      (node (ref "C135") (pin "1") (pinfunction "1_1") (pintype "passive"))
      (node (ref "C78") (pin "1") (pinfunction "1_1") (pintype "passive"))
      (node (ref "C86") (pin "1") (pinfunction "1_1") (pintype "passive"))
      (node (ref "C88") (pin "1") (pinfunction "1_1") (pintype "passive"))
      (node (ref "FB5") (pin "1") (pinfunction "1_1") (pintype "passive"))
      (node (ref "FB7") (pin "1") (pinfunction "1_1") (pintype "passive"))
      (node (ref "R13") (pin "1") (pinfunction "1_1") (pintype "passive"))
      (node (ref "R37") (pin "1") (pinfunction "1_1") (pintype "passive"))
      (node (ref "R46") (pin "1") (pinfunction "1_1") (pintype "passive"))
      (node (ref "U16") (pin "2") (pinfunction "EN_2") (pintype "passive"))
      (node (ref "U16") (pin "3") (pinfunction "VIN_3") (pintype "passive"))
      (node (ref "U17") (pin "2") (pinfunction "EN_2") (pintype "passive"))
      (node (ref "U17") (pin "3") (pinfunction "VIN_3") (pintype "passive"))
    )
    (net (code "17") (name "12v_PER") (class "Default")
      (node (ref "C6") (pin "1") (pinfunction "1_1") (pintype "passive"))
      (node (ref "C7") (pin "1") (pinfunction "1_1") (pintype "passive"))
      (node (ref "C8") (pin "1") (pinfunction "1_1") (pintype "passive"))
      (node (ref "C9") (pin "1") (pinfunction "1_1") (pintype "passive"))
      (node (ref "FB6") (pin "1") (pinfunction "1_1") (pintype "passive"))
      (node (ref "FB8") (pin "1") (pinfunction "1_1") (pintype "passive"))
    )
    (net (code "18") (name "GND") (class "Default")
      (node (ref "C10") (pin "2") (pinfunction "2_2") (pintype "passive"))
      (node (ref "C106") (pin "1") (pinfunction "1_1") (pintype "passive"))
      (node (ref "C107") (pin "1") (pinfunction "1_1") (pintype "passive"))
      (node (ref "C108") (pin "1") (pinfunction "1_1") (pintype "passive"))
      (node (ref "C109") (pin "1") (pinfunction "1_1") (pintype "passive"))
      (node (ref "C11") (pin "1") (pinfunction "1_1") (pintype "passive"))
      (node (ref "C110") (pin "1") (pinfunction "1_1") (pintype "passive"))
      (node (ref "C111") (pin "1") (pinfunction "1_1") (pintype "passive"))
      (node (ref "C113") (pin "1") (pinfunction "1_1") (pintype "passive"))
      (node (ref "C115") (pin "1") (pinfunction "1_1") (pintype "passive"))
      (node (ref "C118") (pin "1") (pinfunction "1_1") (pintype "passive"))
      (node (ref "C12") (pin "1") (pinfunction "1_1") (pintype "passive"))
      (node (ref "C120") (pin "1") (pinfunction "1_1") (pintype "passive"))
      (node (ref "C121") (pin "1") (pinfunction "1_1") (pintype "passive"))
      (node (ref "C122") (pin "1") (pinfunction "1_1") (pintype "passive"))
      (node (ref "C123") (pin "2") (pinfunction "2_2") (pintype "passive"))
      (node (ref "C124") (pin "2") (pinfunction "2_2") (pintype "passive"))
      (node (ref "C125") (pin "2") (pinfunction "2_2") (pintype "passive"))
      (node (ref "C126") (pin "2") (pinfunction "2_2") (pintype "passive"))
      (node (ref "C127") (pin "1") (pinfunction "1_1") (pintype "passive"))
      (node (ref "C128") (pin "1") (pinfunction "1_1") (pintype "passive"))
      (node (ref "C129") (pin "1") (pinfunction "1_1") (pintype "passive"))
      (node (ref "C13") (pin "1") (pinfunction "1_1") (pintype "passive"))
      (node (ref "C130") (pin "1") (pinfunction "1_1") (pintype "passive"))
      (node (ref "C131") (pin "1") (pinfunction "1_1") (pintype "passive"))
      (node (ref "C132") (pin "1") (pinfunction "1_1") (pintype "passive"))
      (node (ref "C134") (pin "2") (pinfunction "2_2") (pintype "passive"))
      (node (ref "C135") (pin "2") (pinfunction "2_2") (pintype "passive"))
      (node (ref "C136") (pin "2") (pinfunction "2_2") (pintype "passive"))
      (node (ref "C137") (pin "2") (pinfunction "2_2") (pintype "passive"))
      (node (ref "C14") (pin "1") (pinfunction "1_1") (pintype "passive"))
      (node (ref "C15") (pin "1") (pinfunction "1_1") (pintype "passive"))
      (node (ref "C16") (pin "1") (pinfunction "1_1") (pintype "passive"))
      (node (ref "C162") (pin "2") (pinfunction "2_2") (pintype "passive"))
      (node (ref "C163") (pin "2") (pinfunction "2_2") (pintype "passive"))
      (node (ref "C17") (pin "1") (pinfunction "1_1") (pintype "passive"))
      (node (ref "C172") (pin "2") (pinfunction "2_2") (pintype "passive"))
      (node (ref "C173") (pin "1") (pinfunction "1_1") (pintype "passive"))
      (node (ref "C18") (pin "1") (pinfunction "1_1") (pintype "passive"))
      (node (ref "C19") (pin "1") (pinfunction "1_1") (pintype "passive"))
      (node (ref "C21") (pin "1") (pinfunction "1_1") (pintype "passive"))
      (node (ref "C22") (pin "1") (pinfunction "1_1") (pintype "passive"))
      (node (ref "C23") (pin "1") (pinfunction "1_1") (pintype "passive"))
      (node (ref "C24") (pin "1") (pinfunction "1_1") (pintype "passive"))
      (node (ref "C26") (pin "1") (pinfunction "1_1") (pintype "passive"))
      (node (ref "C27") (pin "1") (pinfunction "1_1") (pintype "passive"))
      (node (ref "C28") (pin "1") (pinfunction "1_1") (pintype "passive"))
      (node (ref "C29") (pin "1") (pinfunction "1_1") (pintype "passive"))
      (node (ref "C30") (pin "1") (pinfunction "1_1") (pintype "passive"))
      (node (ref "C31") (pin "1") (pinfunction "1_1") (pintype "passive"))
      (node (ref "C33") (pin "1") (pinfunction "1_1") (pintype "passive"))
      (node (ref "C34") (pin "1") (pinfunction "1_1") (pintype "passive"))
      (node (ref "C35") (pin "1") (pinfunction "1_1") (pintype "passive"))
      (node (ref "C36") (pin "1") (pinfunction "1_1") (pintype "passive"))
      (node (ref "C38") (pin "1") (pinfunction "1_1") (pintype "passive"))
      (node (ref "C39") (pin "1") (pinfunction "1_1") (pintype "passive"))
      (node (ref "C40") (pin "1") (pinfunction "1_1") (pintype "passive"))
      (node (ref "C41") (pin "1") (pinfunction "1_1") (pintype "passive"))
      (node (ref "C42") (pin "1") (pinfunction "1_1") (pintype "passive"))
      (node (ref "C43") (pin "1") (pinfunction "1_1") (pintype "passive"))
      (node (ref "C45") (pin "1") (pinfunction "1_1") (pintype "passive"))
      (node (ref "C46") (pin "1") (pinfunction "1_1") (pintype "passive"))
      (node (ref "C49") (pin "1") (pinfunction "1_1") (pintype "passive"))
      (node (ref "C51") (pin "1") (pinfunction "1_1") (pintype "passive"))
      (node (ref "C6") (pin "2") (pinfunction "2_2") (pintype "passive"))
      (node (ref "C66") (pin "1") (pinfunction "1_1") (pintype "passive"))
      (node (ref "C67") (pin "1") (pinfunction "1_1") (pintype "passive"))
      (node (ref "C7") (pin "2") (pinfunction "2_2") (pintype "passive"))
      (node (ref "C78") (pin "2") (pinfunction "2_2") (pintype "passive"))
      (node (ref "C8") (pin "2") (pinfunction "2_2") (pintype "passive"))
      (node (ref "C86") (pin "2") (pinfunction "2_2") (pintype "passive"))
      (node (ref "C88") (pin "2") (pinfunction "2_2") (pintype "passive"))
      (node (ref "C9") (pin "2") (pinfunction "2_2") (pintype "passive"))
      (node (ref "M1") (pin "2") (pinfunction "2_2") (pintype "passive"))
      (node (ref "M1") (pin "3") (pinfunction "3_3") (pintype "passive"))
      (node (ref "M2") (pin "2") (pinfunction "2_2") (pintype "passive"))
      (node (ref "M2") (pin "3") (pinfunction "3_3") (pintype "passive"))
      (node (ref "R11") (pin "1") (pinfunction "1_1") (pintype "passive"))
      (node (ref "R12") (pin "1") (pinfunction "1_1") (pintype "passive"))
      (node (ref "R14") (pin "1") (pinfunction "1_1") (pintype "passive"))
      (node (ref "R15") (pin "1") (pinfunction "1_1") (pintype "passive"))
      (node (ref "R16") (pin "1") (pinfunction "1_1") (pintype "passive"))
      (node (ref "R38") (pin "1") (pinfunction "1_1") (pintype "passive"))
      (node (ref "R45") (pin "1") (pinfunction "1_1") (pintype "passive"))
      (node (ref "R47") (pin "1") (pinfunction "1_1") (pintype "passive"))
      (node (ref "R50") (pin "1") (pinfunction "1_1") (pintype "passive"))
      (node (ref "S1") (pin "1") (pinfunction "1_1") (pintype "passive"))
      (node (ref "S1") (pin "4") (pinfunction "4_4") (pintype "passive"))
      (node (ref "S1") (pin "7") (pinfunction "7_7") (pintype "passive"))
      (node (ref "S2") (pin "1") (pinfunction "1_1") (pintype "passive"))
      (node (ref "S2") (pin "4") (pinfunction "4_4") (pintype "passive"))
      (node (ref "S2") (pin "7") (pinfunction "7_7") (pintype "passive"))
      (node (ref "U10") (pin "44") (pinfunction "VSS_44") (pintype "power_in"))
      (node (ref "U10") (pin "58") (pinfunction "VSS_58") (pintype "power_in"))
      (node (ref "U10") (pin "65") (pinfunction "EXP_VSS_65") (pintype "power_in"))
      (node (ref "U15") (pin "44") (pinfunction "VSS_44") (pintype "power_in"))
      (node (ref "U15") (pin "58") (pinfunction "VSS_58") (pintype "power_in"))
      (node (ref "U15") (pin "65") (pinfunction "EXP_VSS_65") (pintype "power_in"))
      (node (ref "U16") (pin "4") (pinfunction "GND_4") (pintype "power_in"))
      (node (ref "U17") (pin "4") (pinfunction "GND_4") (pintype "power_in"))
      (node (ref "U21") (pin "4") (pinfunction "VSS_4") (pintype "power_in"))
      (node (ref "U22") (pin "4") (pinfunction "VSS_4") (pintype "power_in"))
      (node (ref "U25") (pin "3") (pinfunction "GND_3") (pintype "power_in"))
      (node (ref "U26") (pin "3") (pinfunction "3_3") (pintype "passive"))
      (node (ref "U7") (pin "49") (pinfunction "GND_49") (pintype "power_in"))
      (node (ref "Y2") (pin "2") (pinfunction "GND_2") (pintype "power_in"))
      (node (ref "Y2") (pin "4") (pinfunction "GND_4") (pintype "power_in"))
      (node (ref "Y4") (pin "2") (pinfunction "GND_2") (pintype "power_in"))
      (node (ref "Y4") (pin "4") (pinfunction "GND_4") (pintype "power_in"))
      (node (ref "Y5") (pin "2") (pinfunction "GND_2") (pintype "power_in"))
      (node (ref "Y5") (pin "4") (pinfunction "GND_4") (pintype "power_in"))
    )
    (net (code "19") (name "Net-(FB5-Pad2)") (class "Default")
      (node (ref "FB5") (pin "2") (pinfunction "2_2") (pintype "passive"))
      (node (ref "M1") (pin "1") (pinfunction "1_1") (pintype "passive"))
    )
    (net (code "20") (name "Net-(FB6-Pad2)") (class "Default")
      (node (ref "FB6") (pin "2") (pinfunction "2_2") (pintype "passive"))
      (node (ref "M1") (pin "4") (pinfunction "4_4") (pintype "passive"))
    )
    (net (code "21") (name "Net-(FB7-Pad2)") (class "Default")
      (node (ref "FB7") (pin "2") (pinfunction "2_2") (pintype "passive"))
      (node (ref "M2") (pin "1") (pinfunction "1_1") (pintype "passive"))
    )
    (net (code "22") (name "Net-(FB8-Pad2)") (class "Default")
      (node (ref "FB8") (pin "2") (pinfunction "2_2") (pintype "passive"))
      (node (ref "M2") (pin "4") (pinfunction "4_4") (pintype "passive"))
    )
    (net (code "23") (name "Net-(LED2-Anode)") (class "Default")
      (node (ref "LED2") (pin "2") (pinfunction "Anode_2") (pintype "passive"))
      (node (ref "R40") (pin "1") (pinfunction "1_1") (pintype "passive"))
    )
    (net (code "24") (name "Net-(LED2-Cathode)") (class "Default")
      (node (ref "LED2") (pin "1") (pinfunction "Cathode_1") (pintype "passive"))
      (node (ref "U10") (pin "2") (pinfunction "PWM0_2") (pintype "output"))
    )
    (net (code "25") (name "Net-(LED3-Anode)") (class "Default")
      (node (ref "LED3") (pin "2") (pinfunction "Anode_2") (pintype "passive"))
      (node (ref "R41") (pin "1") (pinfunction "1_1") (pintype "passive"))
    )
    (net (code "26") (name "Net-(LED3-Cathode)") (class "Default")
      (node (ref "LED3") (pin "1") (pinfunction "Cathode_1") (pintype "passive"))
      (node (ref "U10") (pin "3") (pinfunction "PWM1_3") (pintype "output"))
    )
    (net (code "27") (name "Net-(LED4-Anode)") (class "Default")
      (node (ref "LED4") (pin "2") (pinfunction "Anode_2") (pintype "passive"))
      (node (ref "R51") (pin "1") (pinfunction "1_1") (pintype "passive"))
    )
    (net (code "28") (name "Net-(LED4-Cathode)") (class "Default")
      (node (ref "LED4") (pin "1") (pinfunction "Cathode_1") (pintype "passive"))
      (node (ref "U15") (pin "2") (pinfunction "PWM0_2") (pintype "output"))
    )
    (net (code "29") (name "Net-(LED5-Anode)") (class "Default")
      (node (ref "LED5") (pin "2") (pinfunction "Anode_2") (pintype "passive"))
      (node (ref "R52") (pin "1") (pinfunction "1_1") (pintype "passive"))
    )
    (net (code "30") (name "Net-(LED5-Cathode)") (class "Default")
      (node (ref "LED5") (pin "1") (pinfunction "Cathode_1") (pintype "passive"))
      (node (ref "U15") (pin "3") (pinfunction "PWM1_3") (pintype "output"))
    )
    (net (code "31") (name "Net-(R57-Pad1)") (class "Default")
      (node (ref "R57") (pin "1") (pinfunction "1_1") (pintype "passive"))
      (node (ref "U26") (pin "4") (pinfunction "4_4") (pintype "passive"))
    )
    (net (code "32") (name "Net-(R62-Pad1)") (class "Default")
      (node (ref "R62") (pin "1") (pinfunction "1_1") (pintype "passive"))
      (node (ref "U26") (pin "1") (pinfunction "1_1") (pintype "passive"))
    )
    (net (code "33") (name "Net-(U7-GANGED{slash}SMBA2{slash}HS_UP)") (class "Default")
      (node (ref "R15") (pin "2") (pinfunction "2_2") (pintype "passive"))
      (node (ref "U7") (pin "35") (pinfunction "GANGED/SMBA2/HS_UP_35") (pintype "input"))
    )
    (net (code "34") (name "Net-(U7-GRSTZ)") (class "Default")
      (node (ref "C11") (pin "2") (pinfunction "2_2") (pintype "passive"))
      (node (ref "U7") (pin "11") (pinfunction "GRSTZ_11") (pintype "input"))
    )
    (net (code "35") (name "Net-(U7-PWRCRL_POL{slash}SS_DN1)") (class "Default")
      (node (ref "R14") (pin "2") (pinfunction "2_2") (pintype "passive"))
      (node (ref "U7") (pin "21") (pinfunction "PWRCRL_POL/SS_DN1_21") (pintype "bidirectional"))
    )
    (net (code "36") (name "Net-(U7-TEST)") (class "Default")
      (node (ref "R16") (pin "2") (pinfunction "2_2") (pintype "passive"))
      (node (ref "U7") (pin "10") (pinfunction "TEST_10") (pintype "input"))
    )
    (net (code "37") (name "Net-(U7-USB_R1)") (class "Default")
      (node (ref "R11") (pin "2") (pinfunction "2_2") (pintype "passive"))
      (node (ref "U7") (pin "24") (pinfunction "USB_R1_24") (pintype "input"))
    )
    (net (code "38") (name "Net-(U7-USB_SSRXM_DN1)") (class "Default")
      (node (ref "C37") (pin "1") (pinfunction "1_1") (pintype "passive"))
      (node (ref "U7") (pin "47") (pinfunction "USB_SSRXM_DN1_47") (pintype "input"))
    )
    (net (code "39") (name "Net-(U7-USB_SSRXM_DN2)") (class "Default")
      (node (ref "C47") (pin "1") (pinfunction "1_1") (pintype "passive"))
      (node (ref "U7") (pin "20") (pinfunction "USB_SSRXM_DN2_20") (pintype "input"))
    )
    (net (code "40") (name "Net-(U7-USB_SSRXP_DN1)") (class "Default")
      (node (ref "C32") (pin "1") (pinfunction "1_1") (pintype "passive"))
      (node (ref "U7") (pin "46") (pinfunction "USB_SSRXP_DN1_46") (pintype "input"))
    )
    (net (code "41") (name "Net-(U7-USB_SSRXP_DN2)") (class "Default")
      (node (ref "C44") (pin "1") (pinfunction "1_1") (pintype "passive"))
      (node (ref "U7") (pin "19") (pinfunction "USB_SSRXP_DN2_19") (pintype "input"))
    )
    (net (code "42") (name "Net-(U7-USB_SSTXM_DN1)") (class "Default")
      (node (ref "C63") (pin "2") (pinfunction "2_2") (pintype "passive"))
      (node (ref "U7") (pin "44") (pinfunction "USB_SSTXM_DN1_44") (pintype "output"))
    )
    (net (code "43") (name "Net-(U7-USB_SSTXM_DN2)") (class "Default")
      (node (ref "C65") (pin "2") (pinfunction "2_2") (pintype "passive"))
      (node (ref "U7") (pin "17") (pinfunction "USB_SSTXM_DN2_17") (pintype "output"))
    )
    (net (code "44") (name "Net-(U7-USB_SSTXM_UP)") (class "Default")
      (node (ref "C50") (pin "2") (pinfunction "2_2") (pintype "passive"))
      (node (ref "U7") (pin "28") (pinfunction "USB_SSTXM_UP_28") (pintype "output"))
    )
    (net (code "45") (name "Net-(U7-USB_SSTXP_DN1)") (class "Default")
      (node (ref "C52") (pin "2") (pinfunction "2_2") (pintype "passive"))
      (node (ref "U7") (pin "43") (pinfunction "USB_SSTXP_DN1_43") (pintype "output"))
    )
    (net (code "46") (name "Net-(U7-USB_SSTXP_DN2)") (class "Default")
      (node (ref "C64") (pin "2") (pinfunction "2_2") (pintype "passive"))
      (node (ref "U7") (pin "16") (pinfunction "USB_SSTXP_DN2_16") (pintype "output"))
    )
    (net (code "47") (name "Net-(U7-USB_SSTXP_UP)") (class "Default")
      (node (ref "C48") (pin "2") (pinfunction "2_2") (pintype "passive"))
      (node (ref "U7") (pin "29") (pinfunction "USB_SSTXP_UP_29") (pintype "output"))
    )
    (net (code "48") (name "Net-(U7-USB_VBUS)") (class "Default")
      (node (ref "R12") (pin "2") (pinfunction "2_2") (pintype "passive"))
      (node (ref "R13") (pin "2") (pinfunction "2_2") (pintype "passive"))
      (node (ref "U7") (pin "9") (pinfunction "USB_VBUS_9") (pintype "input"))
    )
    (net (code "49") (name "Net-(U7-XI)") (class "Default")
      (node (ref "C66") (pin "2") (pinfunction "2_2") (pintype "passive"))
      (node (ref "R17") (pin "1") (pinfunction "1_1") (pintype "passive"))
      (node (ref "U7") (pin "38") (pinfunction "XI_38") (pintype "input"))
      (node (ref "Y2") (pin "3") (pintype "passive"))
    )
    (net (code "50") (name "Net-(U7-XO)") (class "Default")
      (node (ref "C67") (pin "2") (pinfunction "2_2") (pintype "passive"))
      (node (ref "R17") (pin "2") (pinfunction "2_2") (pintype "passive"))
      (node (ref "U7") (pin "39") (pinfunction "XO_39") (pintype "output"))
      (node (ref "Y2") (pin "1") (pintype "passive"))
    )
    (net (code "51") (name "Net-(U10-FREQSEL0)") (class "Default")
      (node (ref "R35") (pin "2") (pinfunction "2_2") (pintype "passive"))
      (node (ref "U10") (pin "30") (pinfunction "FREQSEL0_30") (pintype "input"))
    )
    (net (code "52") (name "Net-(U10-FREQSEL1)") (class "Default")
      (node (ref "R36") (pin "2") (pinfunction "2_2") (pintype "passive"))
      (node (ref "U10") (pin "31") (pinfunction "FREQSEL1_31") (pintype "input"))
    )
    (net (code "53") (name "Net-(U10-SATA_RXM)") (class "Default")
      (node (ref "C104") (pin "1") (pinfunction "1_1") (pintype "passive"))
      (node (ref "U10") (pin "59") (pinfunction "SATA_RXM_59") (pintype "input"))
    )
    (net (code "54") (name "Net-(U10-SATA_RXP)") (class "Default")
      (node (ref "C102") (pin "1") (pinfunction "1_1") (pintype "passive"))
      (node (ref "U10") (pin "60") (pinfunction "SATA_RXP_60") (pintype "input"))
    )
    (net (code "55") (name "Net-(U10-SATA_TXM)") (class "Default")
      (node (ref "C105") (pin "1") (pinfunction "1_1") (pintype "passive"))
      (node (ref "U10") (pin "56") (pinfunction "SATA_TXM_56") (pintype "output"))
    )
    (net (code "56") (name "Net-(U10-SATA_TXP)") (class "Default")
      (node (ref "C103") (pin "1") (pinfunction "1_1") (pintype "passive"))
      (node (ref "U10") (pin "57") (pinfunction "SATA_TXP_57") (pintype "output"))
    )
    (net (code "57") (name "Net-(U10-USB_R1)") (class "Default")
      (node (ref "R39") (pin "2") (pinfunction "2_2") (pintype "passive"))
      (node (ref "U10") (pin "38") (pinfunction "USB_R1_38") (pintype "output"))
    )
    (net (code "58") (name "Net-(U10-USB_R1RTN)") (class "Default")
      (node (ref "R39") (pin "1") (pinfunction "1_1") (pintype "passive"))
      (node (ref "U10") (pin "39") (pinfunction "USB_R1RTN_39") (pintype "input"))
    )
    (net (code "59") (name "Net-(U10-USB_VBUS)") (class "Default")
      (node (ref "R37") (pin "2") (pinfunction "2_2") (pintype "passive"))
      (node (ref "R38") (pin "2") (pinfunction "2_2") (pintype "passive"))
      (node (ref "U10") (pin "50") (pinfunction "USB_VBUS_50") (pintype "input"))
    )
    (net (code "60") (name "Net-(U10-XI)") (class "Default")
      (node (ref "U10") (pin "52") (pinfunction "XI_52") (pintype "input"))
      (node (ref "Y4") (pin "3") (pintype "passive"))
    )
    (net (code "61") (name "Net-(U10-XO)") (class "Default")
      (node (ref "U10") (pin "54") (pinfunction "XO_54") (pintype "output"))
      (node (ref "Y4") (pin "1") (pintype "passive"))
    )
    (net (code "62") (name "Net-(U15-FREQSEL0)") (class "Default")
      (node (ref "R42") (pin "2") (pinfunction "2_2") (pintype "passive"))
      (node (ref "U15") (pin "30") (pinfunction "FREQSEL0_30") (pintype "input"))
    )
    (net (code "63") (name "Net-(U15-FREQSEL1)") (class "Default")
      (node (ref "R43") (pin "2") (pinfunction "2_2") (pintype "passive"))
      (node (ref "U15") (pin "31") (pinfunction "FREQSEL1_31") (pintype "input"))
    )
    (net (code "64") (name "Net-(U15-SATA_RXM)") (class "Default")
      (node (ref "C117") (pin "1") (pinfunction "1_1") (pintype "passive"))
      (node (ref "U15") (pin "59") (pinfunction "SATA_RXM_59") (pintype "input"))
    )
    (net (code "65") (name "Net-(U15-SATA_RXP)") (class "Default")
      (node (ref "C112") (pin "1") (pinfunction "1_1") (pintype "passive"))
      (node (ref "U15") (pin "60") (pinfunction "SATA_RXP_60") (pintype "input"))
    )
    (net (code "66") (name "Net-(U15-SATA_TXM)") (class "Default")
      (node (ref "C119") (pin "1") (pinfunction "1_1") (pintype "passive"))
      (node (ref "U15") (pin "56") (pinfunction "SATA_TXM_56") (pintype "output"))
    )
    (net (code "67") (name "Net-(U15-SATA_TXP)") (class "Default")
      (node (ref "C114") (pin "1") (pinfunction "1_1") (pintype "passive"))
      (node (ref "U15") (pin "57") (pinfunction "SATA_TXP_57") (pintype "output"))
    )
    (net (code "68") (name "Net-(U15-USB_R1)") (class "Default")
      (node (ref "R48") (pin "2") (pinfunction "2_2") (pintype "passive"))
      (node (ref "U15") (pin "38") (pinfunction "USB_R1_38") (pintype "output"))
    )
    (net (code "69") (name "Net-(U15-USB_R1RTN)") (class "Default")
      (node (ref "R48") (pin "1") (pinfunction "1_1") (pintype "passive"))
      (node (ref "U15") (pin "39") (pinfunction "USB_R1RTN_39") (pintype "input"))
    )
    (net (code "70") (name "Net-(U15-USB_VBUS)") (class "Default")
      (node (ref "R46") (pin "2") (pinfunction "2_2") (pintype "passive"))
      (node (ref "R47") (pin "2") (pinfunction "2_2") (pintype "passive"))
      (node (ref "U15") (pin "50") (pinfunction "USB_VBUS_50") (pintype "input"))
    )
    (net (code "71") (name "Net-(U15-XI)") (class "Default")
      (node (ref "U15") (pin "52") (pinfunction "XI_52") (pintype "input"))
      (node (ref "Y5") (pin "3") (pintype "passive"))
    )
    (net (code "72") (name "Net-(U15-XO)") (class "Default")
      (node (ref "U15") (pin "54") (pinfunction "XO_54") (pintype "output"))
      (node (ref "Y5") (pin "1") (pintype "passive"))
    )
    (net (code "73") (name "Net-(U16-BST)") (class "Default")
      (node (ref "C116") (pin "1") (pinfunction "1_1") (pintype "passive"))
      (node (ref "U16") (pin "6") (pinfunction "BST_6") (pintype "passive"))
    )
    (net (code "74") (name "Net-(U16-FB)") (class "Default")
      (node (ref "R44") (pin "2") (pinfunction "2_2") (pintype "passive"))
      (node (ref "R45") (pin "2") (pinfunction "2_2") (pintype "passive"))
      (node (ref "U16") (pin "1") (pinfunction "FB_1") (pintype "passive"))
    )
    (net (code "75") (name "Net-(U16-SW)") (class "Default")
      (node (ref "C116") (pin "2") (pinfunction "2_2") (pintype "passive"))
      (node (ref "L13") (pin "1") (pinfunction "1_1") (pintype "passive"))
      (node (ref "U16") (pin "5") (pinfunction "SW_5") (pintype "passive"))
    )
    (net (code "76") (name "Net-(U17-BST)") (class "Default")
      (node (ref "C133") (pin "1") (pinfunction "1_1") (pintype "passive"))
      (node (ref "U17") (pin "6") (pinfunction "BST_6") (pintype "passive"))
    )
    (net (code "77") (name "Net-(U17-FB)") (class "Default")
      (node (ref "R49") (pin "2") (pinfunction "2_2") (pintype "passive"))
      (node (ref "R50") (pin "2") (pinfunction "2_2") (pintype "passive"))
      (node (ref "U17") (pin "1") (pinfunction "FB_1") (pintype "passive"))
    )
    (net (code "78") (name "Net-(U17-SW)") (class "Default")
      (node (ref "C133") (pin "2") (pinfunction "2_2") (pintype "passive"))
      (node (ref "L14") (pin "1") (pinfunction "1_1") (pintype "passive"))
      (node (ref "U17") (pin "5") (pinfunction "SW_5") (pintype "passive"))
    )
    (net (code "79") (name "Net-(U21-*HOLD)") (class "Default")
      (node (ref "R110") (pin "2") (pinfunction "2_2") (pintype "passive"))
      (node (ref "U21") (pin "7") (pinfunction "*HOLD_7") (pintype "passive"))
    )
    (net (code "80") (name "Net-(U21-*WP)") (class "Default")
      (node (ref "R109") (pin "2") (pinfunction "2_2") (pintype "passive"))
      (node (ref "U21") (pin "3") (pinfunction "*WP_3") (pintype "passive"))
    )
    (net (code "81") (name "Net-(U22-*HOLD)") (class "Default")
      (node (ref "R112") (pin "2") (pinfunction "2_2") (pintype "passive"))
      (node (ref "U22") (pin "7") (pinfunction "*HOLD_7") (pintype "passive"))
    )
    (net (code "82") (name "Net-(U22-*WP)") (class "Default")
      (node (ref "R111") (pin "2") (pinfunction "2_2") (pintype "passive"))
      (node (ref "U22") (pin "3") (pinfunction "*WP_3") (pintype "passive"))
    )
    (net (code "83") (name "Net-(U25-CT)") (class "Default")
      (node (ref "C172") (pin "1") (pinfunction "1_1") (pintype "passive"))
      (node (ref "U25") (pin "5") (pinfunction "CT_5") (pintype "input"))
    )
    (net (code "84") (name "Net-(U25-RST_N)") (class "Default")
      (node (ref "U25") (pin "1") (pinfunction "RST_N_1") (pintype "open_collector"))
      (node (ref "U26") (pin "2") (pinfunction "2_2") (pintype "passive"))
    )
    (net (code "85") (name "S1_RX_N") (class "Default")
      (node (ref "C104") (pin "2") (pinfunction "2_2") (pintype "passive"))
      (node (ref "S1") (pin "5") (pinfunction "5_5") (pintype "passive"))
    )
    (net (code "86") (name "S1_RX_P") (class "Default")
      (node (ref "C102") (pin "2") (pinfunction "2_2") (pintype "passive"))
      (node (ref "S1") (pin "6") (pinfunction "6_6") (pintype "passive"))
    )
    (net (code "87") (name "S1_TX_N") (class "Default")
      (node (ref "C105") (pin "2") (pinfunction "2_2") (pintype "passive"))
      (node (ref "S1") (pin "3") (pinfunction "3_3") (pintype "passive"))
    )
    (net (code "88") (name "S1_TX_P") (class "Default")
      (node (ref "C103") (pin "2") (pinfunction "2_2") (pintype "passive"))
      (node (ref "S1") (pin "2") (pinfunction "2_2") (pintype "passive"))
    )
    (net (code "89") (name "S2_RX_N") (class "Default")
      (node (ref "C117") (pin "2") (pinfunction "2_2") (pintype "passive"))
      (node (ref "S2") (pin "5") (pinfunction "5_5") (pintype "passive"))
    )
    (net (code "90") (name "S2_RX_P") (class "Default")
      (node (ref "C112") (pin "2") (pinfunction "2_2") (pintype "passive"))
      (node (ref "S2") (pin "6") (pinfunction "6_6") (pintype "passive"))
    )
    (net (code "91") (name "S2_TX_N") (class "Default")
      (node (ref "C119") (pin "2") (pinfunction "2_2") (pintype "passive"))
      (node (ref "S2") (pin "3") (pinfunction "3_3") (pintype "passive"))
    )
    (net (code "92") (name "S2_TX_P") (class "Default")
      (node (ref "C114") (pin "2") (pinfunction "2_2") (pintype "passive"))
      (node (ref "S2") (pin "2") (pinfunction "2_2") (pintype "passive"))
    )
    (net (code "93") (name "SPI_CE_A") (class "Default")
      (node (ref "U10") (pin "21") (pinfunction "SPI_CS0_21") (pintype "output"))
      (node (ref "U21") (pin "1") (pinfunction "*CS_1") (pintype "passive"))
    )
    (net (code "94") (name "SPI_CE_B") (class "Default")
      (node (ref "U15") (pin "21") (pinfunction "SPI_CS0_21") (pintype "output"))
      (node (ref "U22") (pin "1") (pinfunction "*CS_1") (pintype "passive"))
    )
    (net (code "95") (name "SPI_SCK_A") (class "Default")
      (node (ref "U10") (pin "17") (pinfunction "SPI_SCLK_17") (pintype "output"))
      (node (ref "U21") (pin "6") (pinfunction "SCK_6") (pintype "bidirectional"))
    )
    (net (code "96") (name "SPI_SCK_B") (class "Default")
      (node (ref "U15") (pin "17") (pinfunction "SPI_SCLK_17") (pintype "output"))
      (node (ref "U22") (pin "6") (pinfunction "SCK_6") (pintype "bidirectional"))
    )
    (net (code "97") (name "SPI_SI_A") (class "Default")
      (node (ref "U10") (pin "20") (pinfunction "SPI_DATA_IN_20") (pintype "input"))
      (node (ref "U21") (pin "2") (pinfunction "SO_2") (pintype "output"))
    )
    (net (code "98") (name "SPI_SI_B") (class "Default")
      (node (ref "U15") (pin "20") (pinfunction "SPI_DATA_IN_20") (pintype "input"))
      (node (ref "U22") (pin "2") (pinfunction "SO_2") (pintype "output"))
    )
    (net (code "99") (name "SPI_SO_A") (class "Default")
      (node (ref "U10") (pin "18") (pinfunction "SPI_DATA_OUT_18") (pintype "output"))
      (node (ref "U21") (pin "5") (pinfunction "SI_5") (pintype "input"))
    )
    (net (code "100") (name "SPI_SO_B") (class "Default")
      (node (ref "U15") (pin "18") (pinfunction "SPI_DATA_OUT_18") (pintype "output"))
      (node (ref "U22") (pin "5") (pinfunction "SI_5") (pintype "input"))
    )
    (net (code "101") (name "S_RST") (class "Default")
      (node (ref "C173") (pin "2") (pinfunction "2_2") (pintype "passive"))
      (node (ref "R57") (pin "2") (pinfunction "2_2") (pintype "passive"))
      (node (ref "R71") (pin "2") (pinfunction "2_2") (pintype "passive"))
      (node (ref "U10") (pin "4") (pinfunction "GRSTZ_4") (pintype "input"))
      (node (ref "U15") (pin "4") (pinfunction "GRSTZ_4") (pintype "input"))
    )
    (net (code "102") (name "USB3-0-D_N") (class "Default")
      (node (ref "U7") (pin "27") (pinfunction "USB_DM_UP_27") (pintype "bidirectional"))
    )
    (net (code "103") (name "USB3-0-D_P") (class "Default")
      (node (ref "U7") (pin "26") (pinfunction "USB_DP_UP_26") (pintype "bidirectional"))
    )
    (net (code "104") (name "USB3-0-RX_N") (class "Default")
      (node (ref "C50") (pin "1") (pinfunction "1_1") (pintype "passive"))
    )
    (net (code "105") (name "USB3-0-RX_P") (class "Default")
      (node (ref "C48") (pin "1") (pinfunction "1_1") (pintype "passive"))
    )
    (net (code "106") (name "USB3-0-TX_N") (class "Default")
      (node (ref "U7") (pin "31") (pinfunction "USB_SSRXM_UP_31") (pintype "input"))
    )
    (net (code "107") (name "USB3-0-TX_P") (class "Default")
      (node (ref "U7") (pin "32") (pinfunction "USB_SSRXP_UP_32") (pintype "input"))
    )
    (net (code "108") (name "unconnected-(U7-FULLPWRMGMTZ{slash}SMBA1{slash}SS_UP-Pad36)") (class "Default")
      (node (ref "U7") (pin "36") (pinfunction "FULLPWRMGMTZ/SMBA1/SS_UP_36") (pintype "input"))
    )
    (net (code "109") (name "unconnected-(U7-OVERCUR1Z-Pad5)") (class "Default")
      (node (ref "U7") (pin "5") (pinfunction "OVERCUR1Z_5") (pintype "input"))
    )
    (net (code "110") (name "unconnected-(U7-OVERCUR2Z-Pad8)") (class "Default")
      (node (ref "U7") (pin "8") (pinfunction "OVERCUR2Z_8") (pintype "input"))
    )
    (net (code "111") (name "unconnected-(U7-PWRCTL1{slash}BATEN1-Pad4)") (class "Default")
      (node (ref "U7") (pin "4") (pinfunction "PWRCTL1/BATEN1_4") (pintype "bidirectional"))
    )
    (net (code "112") (name "unconnected-(U7-PWRCTL2{slash}BATEN2-Pad6)") (class "Default")
      (node (ref "U7") (pin "6") (pinfunction "PWRCTL2/BATEN2_6") (pintype "bidirectional"))
    )
    (net (code "113") (name "unconnected-(U7-SCL{slash}SMBCLK-Pad2)") (class "Default")
      (node (ref "U7") (pin "2") (pinfunction "SCL/SMBCLK_2") (pintype "bidirectional"))
    )
    (net (code "114") (name "unconnected-(U7-SDA{slash}SMBDAT-Pad3)") (class "Default")
      (node (ref "U7") (pin "3") (pinfunction "SDA/SMBDAT_3") (pintype "bidirectional"))
    )
    (net (code "115") (name "unconnected-(U7-SMBUSZ{slash}SS_DN2-Pad22)") (class "Default")
      (node (ref "U7") (pin "22") (pinfunction "SMBUSZ/SS_DN2_22") (pintype "input"))
    )
    (net (code "116") (name "unconnected-(U10-GPIO0-Pad8)") (class "Default")
      (node (ref "U10") (pin "8") (pinfunction "GPIO0_8") (pintype "bidirectional"))
    )
    (net (code "117") (name "unconnected-(U10-GPIO1-Pad9)") (class "Default")
      (node (ref "U10") (pin "9") (pinfunction "GPIO1_9") (pintype "bidirectional"))
    )
    (net (code "118") (name "unconnected-(U10-GPIO2-Pad10)") (class "Default")
      (node (ref "U10") (pin "10") (pinfunction "GPIO2_10") (pintype "bidirectional"))
    )
    (net (code "119") (name "unconnected-(U10-GPIO3-Pad11)") (class "Default")
      (node (ref "U10") (pin "11") (pinfunction "GPIO3_11") (pintype "bidirectional"))
    )
    (net (code "120") (name "unconnected-(U10-GPIO4-Pad13)") (class "Default")
      (node (ref "U10") (pin "13") (pinfunction "GPIO4_13") (pintype "bidirectional"))
    )
    (net (code "121") (name "unconnected-(U10-GPIO5-Pad14)") (class "Default")
      (node (ref "U10") (pin "14") (pinfunction "GPIO5_14") (pintype "bidirectional"))
    )
    (net (code "122") (name "unconnected-(U10-GPIO6-Pad15)") (class "Default")
      (node (ref "U10") (pin "15") (pinfunction "GPIO6_15") (pintype "bidirectional"))
    )
    (net (code "123") (name "unconnected-(U10-GPIO7-Pad16)") (class "Default")
      (node (ref "U10") (pin "16") (pinfunction "GPIO7_16") (pintype "bidirectional"))
    )
    (net (code "124") (name "unconnected-(U10-GPIO8{slash}UART_RX-Pad5)") (class "Default")
      (node (ref "U10") (pin "5") (pinfunction "GPIO8/UART_RX_5") (pintype "bidirectional"))
    )
    (net (code "125") (name "unconnected-(U10-GPIO9{slash}UART_TX-Pad6)") (class "Default")
      (node (ref "U10") (pin "6") (pinfunction "GPIO9/UART_TX_6") (pintype "bidirectional"))
    )
    (net (code "126") (name "unconnected-(U10-JTAG_TCK-Pad25)") (class "Default")
      (node (ref "U10") (pin "25") (pinfunction "JTAG_TCK_25") (pintype "input"))
    )
    (net (code "127") (name "unconnected-(U10-JTAG_TDI-Pad26)") (class "Default")
      (node (ref "U10") (pin "26") (pinfunction "JTAG_TDI_26") (pintype "input"))
    )
    (net (code "128") (name "unconnected-(U10-JTAG_TDO-Pad27)") (class "Default")
      (node (ref "U10") (pin "27") (pinfunction "JTAG_TDO_27") (pintype "output"))
    )
    (net (code "129") (name "unconnected-(U10-JTAG_TMS-Pad28)") (class "Default")
      (node (ref "U10") (pin "28") (pinfunction "JTAG_TMS_28") (pintype "input"))
    )
    (net (code "130") (name "unconnected-(U10-JTAG_TRSTZ-Pad29)") (class "Default")
      (node (ref "U10") (pin "29") (pinfunction "JTAG_TRSTZ_29") (pintype "input"))
    )
    (net (code "131") (name "unconnected-(U10-SPI_CS1{slash}GPIO10-Pad22)") (class "Default")
      (node (ref "U10") (pin "22") (pinfunction "SPI_CS1/GPIO10_22") (pintype "bidirectional"))
    )
    (net (code "132") (name "unconnected-(U10-SPI_CS2{slash}GPIO11-Pad23)") (class "Default")
      (node (ref "U10") (pin "23") (pinfunction "SPI_CS2/GPIO11_23") (pintype "bidirectional"))
    )
    (net (code "133") (name "unconnected-(U10-VSSOSC-Pad53)") (class "Default")
      (node (ref "U10") (pin "53") (pinfunction "VSSOSC_53") (pintype "power_in"))
    )
    (net (code "134") (name "unconnected-(U15-GPIO0-Pad8)") (class "Default")
      (node (ref "U15") (pin "8") (pinfunction "GPIO0_8") (pintype "bidirectional"))
    )
    (net (code "135") (name "unconnected-(U15-GPIO1-Pad9)") (class "Default")
      (node (ref "U15") (pin "9") (pinfunction "GPIO1_9") (pintype "bidirectional"))
    )
    (net (code "136") (name "unconnected-(U15-GPIO2-Pad10)") (class "Default")
      (node (ref "U15") (pin "10") (pinfunction "GPIO2_10") (pintype "bidirectional"))
    )
    (net (code "137") (name "unconnected-(U15-GPIO3-Pad11)") (class "Default")
      (node (ref "U15") (pin "11") (pinfunction "GPIO3_11") (pintype "bidirectional"))
    )
    (net (code "138") (name "unconnected-(U15-GPIO4-Pad13)") (class "Default")
      (node (ref "U15") (pin "13") (pinfunction "GPIO4_13") (pintype "bidirectional"))
    )
    (net (code "139") (name "unconnected-(U15-GPIO5-Pad14)") (class "Default")
      (node (ref "U15") (pin "14") (pinfunction "GPIO5_14") (pintype "bidirectional"))
    )
    (net (code "140") (name "unconnected-(U15-GPIO6-Pad15)") (class "Default")
      (node (ref "U15") (pin "15") (pinfunction "GPIO6_15") (pintype "bidirectional"))
    )
    (net (code "141") (name "unconnected-(U15-GPIO7-Pad16)") (class "Default")
      (node (ref "U15") (pin "16") (pinfunction "GPIO7_16") (pintype "bidirectional"))
    )
    (net (code "142") (name "unconnected-(U15-GPIO8{slash}UART_RX-Pad5)") (class "Default")
      (node (ref "U15") (pin "5") (pinfunction "GPIO8/UART_RX_5") (pintype "bidirectional"))
    )
    (net (code "143") (name "unconnected-(U15-GPIO9{slash}UART_TX-Pad6)") (class "Default")
      (node (ref "U15") (pin "6") (pinfunction "GPIO9/UART_TX_6") (pintype "bidirectional"))
    )
    (net (code "144") (name "unconnected-(U15-JTAG_TCK-Pad25)") (class "Default")
      (node (ref "U15") (pin "25") (pinfunction "JTAG_TCK_25") (pintype "input"))
    )
    (net (code "145") (name "unconnected-(U15-JTAG_TDI-Pad26)") (class "Default")
      (node (ref "U15") (pin "26") (pinfunction "JTAG_TDI_26") (pintype "input"))
    )
    (net (code "146") (name "unconnected-(U15-JTAG_TDO-Pad27)") (class "Default")
      (node (ref "U15") (pin "27") (pinfunction "JTAG_TDO_27") (pintype "output"))
    )
    (net (code "147") (name "unconnected-(U15-JTAG_TMS-Pad28)") (class "Default")
      (node (ref "U15") (pin "28") (pinfunction "JTAG_TMS_28") (pintype "input"))
    )
    (net (code "148") (name "unconnected-(U15-JTAG_TRSTZ-Pad29)") (class "Default")
      (node (ref "U15") (pin "29") (pinfunction "JTAG_TRSTZ_29") (pintype "input"))
    )
    (net (code "149") (name "unconnected-(U15-SPI_CS1{slash}GPIO10-Pad22)") (class "Default")
      (node (ref "U15") (pin "22") (pinfunction "SPI_CS1/GPIO10_22") (pintype "bidirectional"))
    )
    (net (code "150") (name "unconnected-(U15-SPI_CS2{slash}GPIO11-Pad23)") (class "Default")
      (node (ref "U15") (pin "23") (pinfunction "SPI_CS2/GPIO11_23") (pintype "bidirectional"))
    )
    (net (code "151") (name "unconnected-(U15-VSSOSC-Pad53)") (class "Default")
      (node (ref "U15") (pin "53") (pinfunction "VSSOSC_53") (pintype "power_in"))
    )
    (net (code "152") (name "unconnected-(U25-MR_N-Pad4)") (class "Default")
      (node (ref "U25") (pin "4") (pinfunction "MR_N_4") (pintype "input"))
    )
  )
)
